# das48.net
KiCad netlist of a schematic drawn in EAGLE
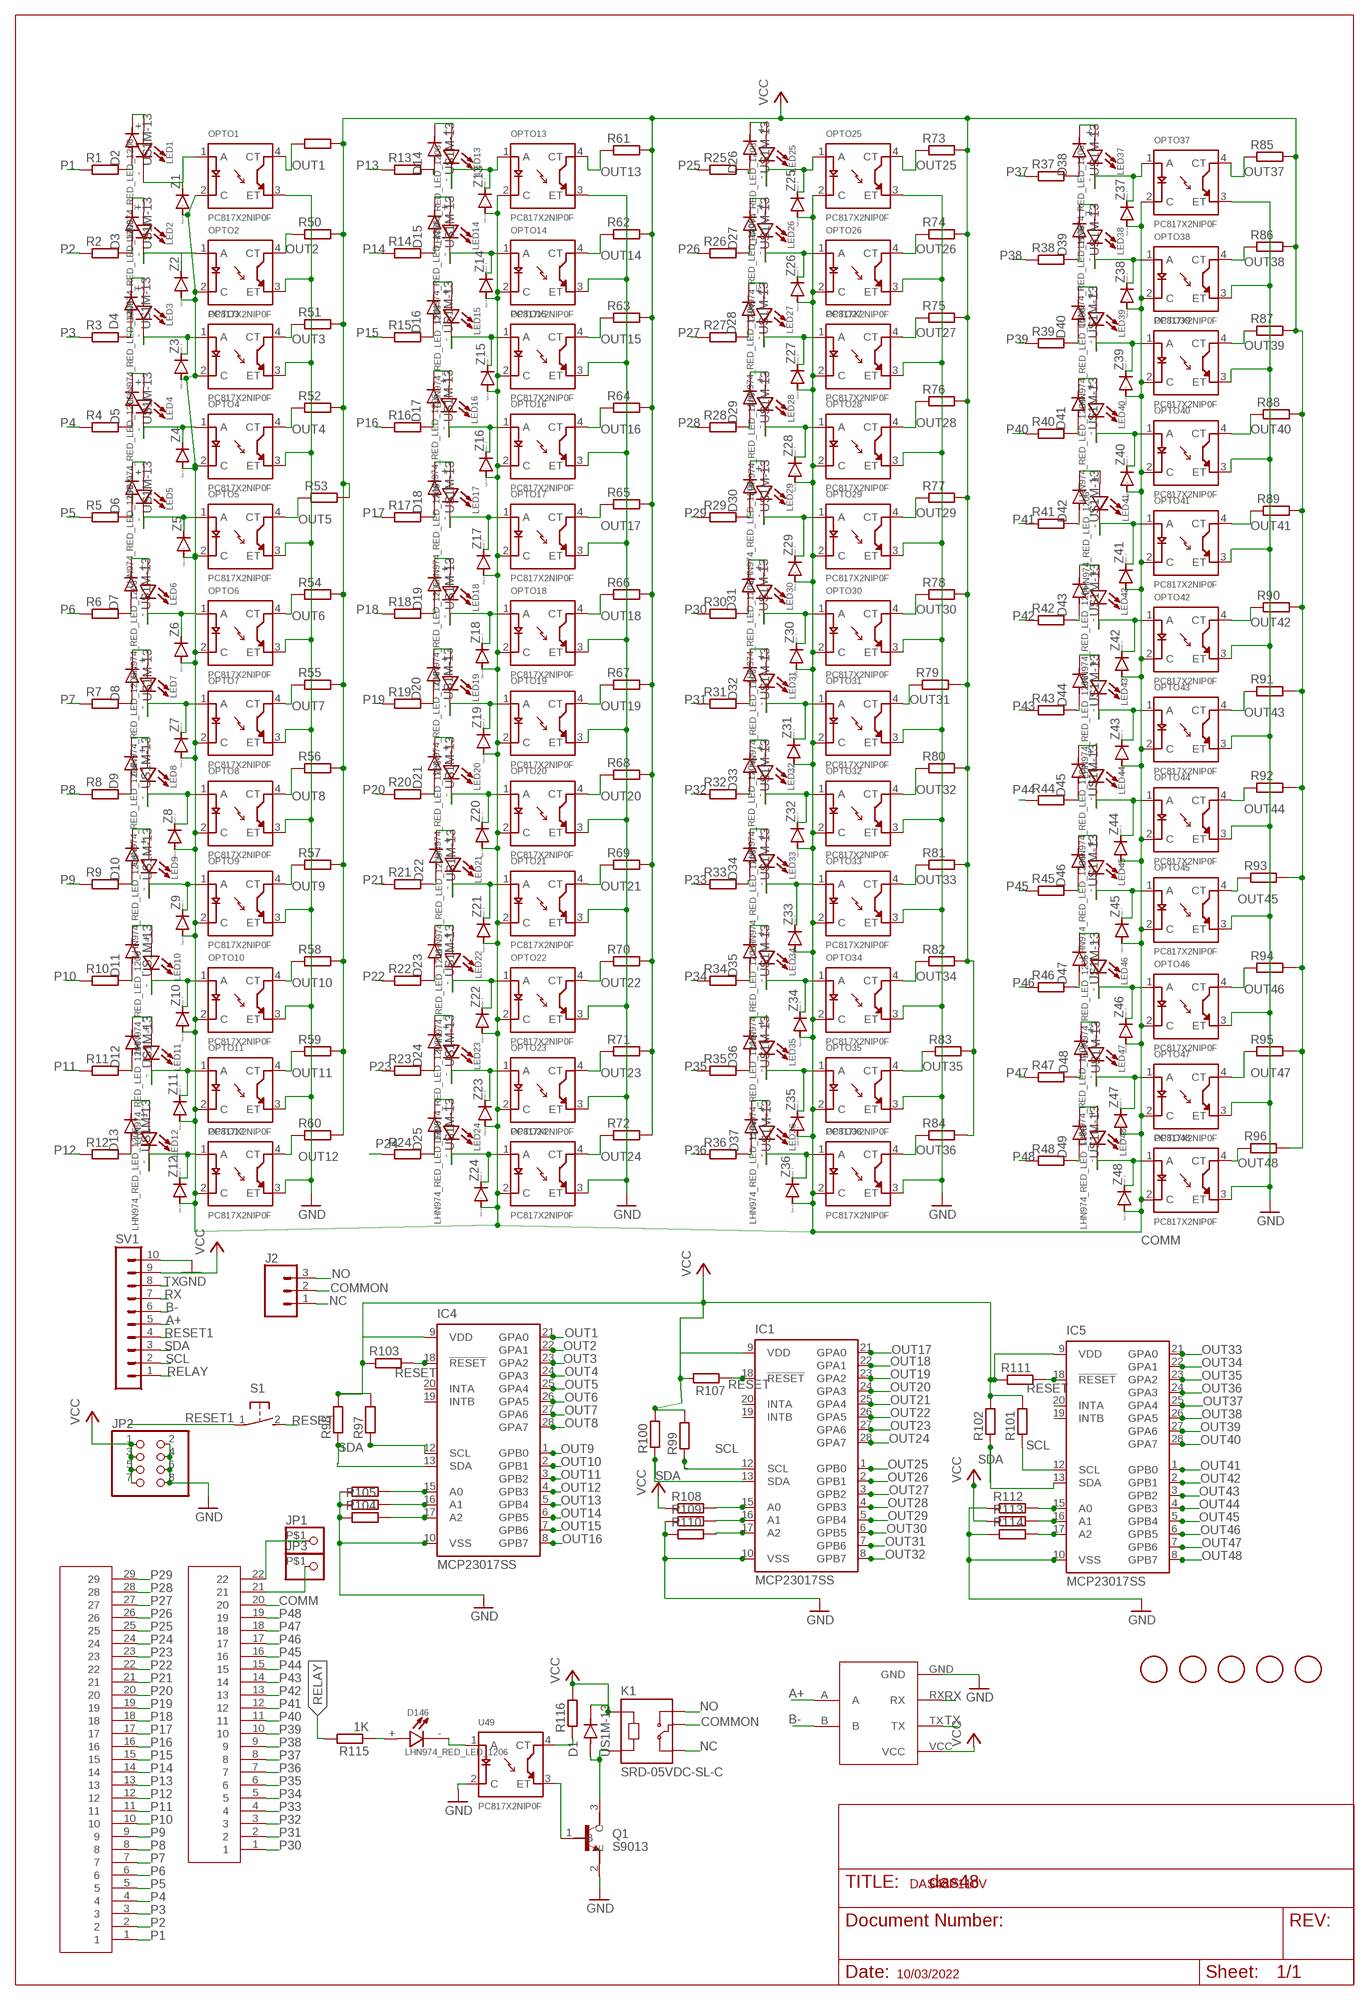
[diagram p0: schematic, sheet 1]

(export (version "E")
  (design (tool "Eeschema 10.0.6"))
  (components
    (comp (ref "D1")
      (value "US1M-13")
      (footprint "eagle-import:DIOM5226X240N")
      (fields (field (name "MF") "Diodes Incorporated"))
      (libsource (lib "eagle-import") (part "US1M-13"))
    )
    (comp (ref "D2")
      (value "US1M-13")
      (footprint "eagle-import:DIOM5226X240N")
      (fields (field (name "MF") "Diodes Incorporated"))
      (libsource (lib "eagle-import") (part "US1M-13"))
    )
    (comp (ref "D3")
      (value "US1M-13")
      (footprint "eagle-import:DIOM5226X240N")
      (fields (field (name "MF") "Diodes Incorporated"))
      (libsource (lib "eagle-import") (part "US1M-13"))
    )
    (comp (ref "D4")
      (value "US1M-13")
      (footprint "eagle-import:DIOM5226X240N")
      (fields (field (name "MF") "Diodes Incorporated"))
      (libsource (lib "eagle-import") (part "US1M-13"))
    )
    (comp (ref "D5")
      (value "US1M-13")
      (footprint "eagle-import:DIOM5226X240N")
      (fields (field (name "MF") "Diodes Incorporated"))
      (libsource (lib "eagle-import") (part "US1M-13"))
    )
    (comp (ref "D6")
      (value "US1M-13")
      (footprint "eagle-import:DIOM5226X240N")
      (fields (field (name "MF") "Diodes Incorporated"))
      (libsource (lib "eagle-import") (part "US1M-13"))
    )
    (comp (ref "D7")
      (value "US1M-13")
      (footprint "eagle-import:DIOM5226X240N")
      (fields (field (name "MF") "Diodes Incorporated"))
      (libsource (lib "eagle-import") (part "US1M-13"))
    )
    (comp (ref "D8")
      (value "US1M-13")
      (footprint "eagle-import:DIOM5226X240N")
      (fields (field (name "MF") "Diodes Incorporated"))
      (libsource (lib "eagle-import") (part "US1M-13"))
    )
    (comp (ref "D9")
      (value "US1M-13")
      (footprint "eagle-import:DIOM5226X240N")
      (fields (field (name "MF") "Diodes Incorporated"))
      (libsource (lib "eagle-import") (part "US1M-13"))
    )
    (comp (ref "D10")
      (value "US1M-13")
      (footprint "eagle-import:DIOM5226X240N")
      (fields (field (name "MF") "Diodes Incorporated"))
      (libsource (lib "eagle-import") (part "US1M-13"))
    )
    (comp (ref "D11")
      (value "US1M-13")
      (footprint "eagle-import:DIOM5226X240N")
      (fields (field (name "MF") "Diodes Incorporated"))
      (libsource (lib "eagle-import") (part "US1M-13"))
    )
    (comp (ref "D12")
      (value "US1M-13")
      (footprint "eagle-import:DIOM5226X240N")
      (fields (field (name "MF") "Diodes Incorporated"))
      (libsource (lib "eagle-import") (part "US1M-13"))
    )
    (comp (ref "D13")
      (value "US1M-13")
      (footprint "eagle-import:DIOM5226X240N")
      (fields (field (name "MF") "Diodes Incorporated"))
      (libsource (lib "eagle-import") (part "US1M-13"))
    )
    (comp (ref "D14")
      (value "US1M-13")
      (footprint "eagle-import:DIOM5226X240N")
      (fields (field (name "MF") "Diodes Incorporated"))
      (libsource (lib "eagle-import") (part "US1M-13"))
    )
    (comp (ref "D15")
      (value "US1M-13")
      (footprint "eagle-import:DIOM5226X240N")
      (fields (field (name "MF") "Diodes Incorporated"))
      (libsource (lib "eagle-import") (part "US1M-13"))
    )
    (comp (ref "D16")
      (value "US1M-13")
      (footprint "eagle-import:DIOM5226X240N")
      (fields (field (name "MF") "Diodes Incorporated"))
      (libsource (lib "eagle-import") (part "US1M-13"))
    )
    (comp (ref "D17")
      (value "US1M-13")
      (footprint "eagle-import:DIOM5226X240N")
      (fields (field (name "MF") "Diodes Incorporated"))
      (libsource (lib "eagle-import") (part "US1M-13"))
    )
    (comp (ref "D18")
      (value "US1M-13")
      (footprint "eagle-import:DIOM5226X240N")
      (fields (field (name "MF") "Diodes Incorporated"))
      (libsource (lib "eagle-import") (part "US1M-13"))
    )
    (comp (ref "D19")
      (value "US1M-13")
      (footprint "eagle-import:DIOM5226X240N")
      (fields (field (name "MF") "Diodes Incorporated"))
      (libsource (lib "eagle-import") (part "US1M-13"))
    )
    (comp (ref "D20")
      (value "US1M-13")
      (footprint "eagle-import:DIOM5226X240N")
      (fields (field (name "MF") "Diodes Incorporated"))
      (libsource (lib "eagle-import") (part "US1M-13"))
    )
    (comp (ref "D21")
      (value "US1M-13")
      (footprint "eagle-import:DIOM5226X240N")
      (fields (field (name "MF") "Diodes Incorporated"))
      (libsource (lib "eagle-import") (part "US1M-13"))
    )
    (comp (ref "D22")
      (value "US1M-13")
      (footprint "eagle-import:DIOM5226X240N")
      (fields (field (name "MF") "Diodes Incorporated"))
      (libsource (lib "eagle-import") (part "US1M-13"))
    )
    (comp (ref "D23")
      (value "US1M-13")
      (footprint "eagle-import:DIOM5226X240N")
      (fields (field (name "MF") "Diodes Incorporated"))
      (libsource (lib "eagle-import") (part "US1M-13"))
    )
    (comp (ref "D24")
      (value "US1M-13")
      (footprint "eagle-import:DIOM5226X240N")
      (fields (field (name "MF") "Diodes Incorporated"))
      (libsource (lib "eagle-import") (part "US1M-13"))
    )
    (comp (ref "D25")
      (value "US1M-13")
      (footprint "eagle-import:DIOM5226X240N")
      (fields (field (name "MF") "Diodes Incorporated"))
      (libsource (lib "eagle-import") (part "US1M-13"))
    )
    (comp (ref "D26")
      (value "US1M-13")
      (footprint "eagle-import:DIOM5226X240N")
      (fields (field (name "MF") "Diodes Incorporated"))
      (libsource (lib "eagle-import") (part "US1M-13"))
    )
    (comp (ref "D27")
      (value "US1M-13")
      (footprint "eagle-import:DIOM5226X240N")
      (fields (field (name "MF") "Diodes Incorporated"))
      (libsource (lib "eagle-import") (part "US1M-13"))
    )
    (comp (ref "D28")
      (value "US1M-13")
      (footprint "eagle-import:DIOM5226X240N")
      (fields (field (name "MF") "Diodes Incorporated"))
      (libsource (lib "eagle-import") (part "US1M-13"))
    )
    (comp (ref "D29")
      (value "US1M-13")
      (footprint "eagle-import:DIOM5226X240N")
      (fields (field (name "MF") "Diodes Incorporated"))
      (libsource (lib "eagle-import") (part "US1M-13"))
    )
    (comp (ref "D30")
      (value "US1M-13")
      (footprint "eagle-import:DIOM5226X240N")
      (fields (field (name "MF") "Diodes Incorporated"))
      (libsource (lib "eagle-import") (part "US1M-13"))
    )
    (comp (ref "D31")
      (value "US1M-13")
      (footprint "eagle-import:DIOM5226X240N")
      (fields (field (name "MF") "Diodes Incorporated"))
      (libsource (lib "eagle-import") (part "US1M-13"))
    )
    (comp (ref "D32")
      (value "US1M-13")
      (footprint "eagle-import:DIOM5226X240N")
      (fields (field (name "MF") "Diodes Incorporated"))
      (libsource (lib "eagle-import") (part "US1M-13"))
    )
    (comp (ref "D33")
      (value "US1M-13")
      (footprint "eagle-import:DIOM5226X240N")
      (fields (field (name "MF") "Diodes Incorporated"))
      (libsource (lib "eagle-import") (part "US1M-13"))
    )
    (comp (ref "D34")
      (value "US1M-13")
      (footprint "eagle-import:DIOM5226X240N")
      (fields (field (name "MF") "Diodes Incorporated"))
      (libsource (lib "eagle-import") (part "US1M-13"))
    )
    (comp (ref "D35")
      (value "US1M-13")
      (footprint "eagle-import:DIOM5226X240N")
      (fields (field (name "MF") "Diodes Incorporated"))
      (libsource (lib "eagle-import") (part "US1M-13"))
    )
    (comp (ref "D36")
      (value "US1M-13")
      (footprint "eagle-import:DIOM5226X240N")
      (fields (field (name "MF") "Diodes Incorporated"))
      (libsource (lib "eagle-import") (part "US1M-13"))
    )
    (comp (ref "D37")
      (value "US1M-13")
      (footprint "eagle-import:DIOM5226X240N")
      (fields (field (name "MF") "Diodes Incorporated"))
      (libsource (lib "eagle-import") (part "US1M-13"))
    )
    (comp (ref "D38")
      (value "US1M-13")
      (footprint "eagle-import:DIOM5226X240N")
      (fields (field (name "MF") "Diodes Incorporated"))
      (libsource (lib "eagle-import") (part "US1M-13"))
    )
    (comp (ref "D39")
      (value "US1M-13")
      (footprint "eagle-import:DIOM5226X240N")
      (fields (field (name "MF") "Diodes Incorporated"))
      (libsource (lib "eagle-import") (part "US1M-13"))
    )
    (comp (ref "D40")
      (value "US1M-13")
      (footprint "eagle-import:DIOM5226X240N")
      (fields (field (name "MF") "Diodes Incorporated"))
      (libsource (lib "eagle-import") (part "US1M-13"))
    )
    (comp (ref "D41")
      (value "US1M-13")
      (footprint "eagle-import:DIOM5226X240N")
      (fields (field (name "MF") "Diodes Incorporated"))
      (libsource (lib "eagle-import") (part "US1M-13"))
    )
    (comp (ref "D42")
      (value "US1M-13")
      (footprint "eagle-import:DIOM5226X240N")
      (fields (field (name "MF") "Diodes Incorporated"))
      (libsource (lib "eagle-import") (part "US1M-13"))
    )
    (comp (ref "D43")
      (value "US1M-13")
      (footprint "eagle-import:DIOM5226X240N")
      (fields (field (name "MF") "Diodes Incorporated"))
      (libsource (lib "eagle-import") (part "US1M-13"))
    )
    (comp (ref "D44")
      (value "US1M-13")
      (footprint "eagle-import:DIOM5226X240N")
      (fields (field (name "MF") "Diodes Incorporated"))
      (libsource (lib "eagle-import") (part "US1M-13"))
    )
    (comp (ref "D45")
      (value "US1M-13")
      (footprint "eagle-import:DIOM5226X240N")
      (fields (field (name "MF") "Diodes Incorporated"))
      (libsource (lib "eagle-import") (part "US1M-13"))
    )
    (comp (ref "D46")
      (value "US1M-13")
      (footprint "eagle-import:DIOM5226X240N")
      (fields (field (name "MF") "Diodes Incorporated"))
      (libsource (lib "eagle-import") (part "US1M-13"))
    )
    (comp (ref "D47")
      (value "US1M-13")
      (footprint "eagle-import:DIOM5226X240N")
      (fields (field (name "MF") "Diodes Incorporated"))
      (libsource (lib "eagle-import") (part "US1M-13"))
    )
    (comp (ref "D48")
      (value "US1M-13")
      (footprint "eagle-import:DIOM5226X240N")
      (fields (field (name "MF") "Diodes Incorporated"))
      (libsource (lib "eagle-import") (part "US1M-13"))
    )
    (comp (ref "D49")
      (value "US1M-13")
      (footprint "eagle-import:DIOM5226X240N")
      (fields (field (name "MF") "Diodes Incorporated"))
      (libsource (lib "eagle-import") (part "US1M-13"))
    )
    (comp (ref "D146")
      (value "LHN974_RED_LED_1206")
      (footprint "eagle-import:LEDC3216X120N")
      (fields (field (name "MF") "Osram") (field (name "MP") "LHN974 RED LED 1206"))
      (libsource (lib "eagle-import") (part "LHN974_RED_LED_1206"))
    )
    (comp (ref "HEADER-22P1")
      (value "HEADER-22P")
      (footprint "eagle-import:HEADER-29P")
      (libsource (lib "eagle-import") (part "HEADER-22P"))
    )
    (comp (ref "HEADER-29P1")
      (value "HEADER-29P")
      (footprint "eagle-import:HEADER-29P")
      (libsource (lib "eagle-import") (part "HEADER-29P"))
    )
    (comp (ref "IC1")
      (value "MCP23017SS")
      (footprint "eagle-import:SSOP28DB")
      (libsource (lib "eagle-import") (part "MCP23017SS"))
    )
    (comp (ref "IC4")
      (value "MCP23017SS")
      (footprint "eagle-import:SSOP28DB")
      (libsource (lib "eagle-import") (part "MCP23017SS"))
    )
    (comp (ref "IC5")
      (value "MCP23017SS")
      (footprint "eagle-import:SSOP28DB")
      (libsource (lib "eagle-import") (part "MCP23017SS"))
    )
    (comp (ref "J2")
      (value "CONN_03LONGPADS")
      (footprint "eagle-import:1X03_LONGPADS")
      (libsource (lib "eagle-import") (part "CONN_03LONGPADS"))
    )
    (comp (ref "JP1")
      (value "PINHD-1X1-BIGPOGO")
      (footprint "eagle-import:1X1-BIGPOGO")
      (libsource (lib "eagle-import") (part "PINHD-1X1-BIGPOGO"))
    )
    (comp (ref "JP2")
      (value "PINHD-2X4")
      (footprint "eagle-import:2X04")
      (libsource (lib "eagle-import") (part "PINHD-2X4"))
    )
    (comp (ref "JP3")
      (value "PINHD-1X1-BIGPOGO")
      (footprint "eagle-import:1X1-BIGPOGO")
      (libsource (lib "eagle-import") (part "PINHD-1X1-BIGPOGO"))
    )
    (comp (ref "K1")
      (value "SRD-05VDC-SL-C")
      (footprint "eagle-import:RELAY_SRD-05VDC-SL-C")
      (fields (field (name "MF") "Songle Relay"))
      (libsource (lib "eagle-import") (part "SRD-05VDC-SL-C"))
    )
    (comp (ref "LED1")
      (value "LHN974_RED_LED_1206")
      (footprint "eagle-import:LEDC3216X120N")
      (fields (field (name "MF") "Osram") (field (name "MP") "LHN974 RED LED 1206"))
      (libsource (lib "eagle-import") (part "LHN974_RED_LED_1206"))
    )
    (comp (ref "LED2")
      (value "LHN974_RED_LED_1206")
      (footprint "eagle-import:LEDC3216X120N")
      (fields (field (name "MF") "Osram") (field (name "MP") "LHN974 RED LED 1206"))
      (libsource (lib "eagle-import") (part "LHN974_RED_LED_1206"))
    )
    (comp (ref "LED3")
      (value "LHN974_RED_LED_1206")
      (footprint "eagle-import:LEDC3216X120N")
      (fields (field (name "MF") "Osram") (field (name "MP") "LHN974 RED LED 1206"))
      (libsource (lib "eagle-import") (part "LHN974_RED_LED_1206"))
    )
    (comp (ref "LED4")
      (value "LHN974_RED_LED_1206")
      (footprint "eagle-import:LEDC3216X120N")
      (fields (field (name "MF") "Osram") (field (name "MP") "LHN974 RED LED 1206"))
      (libsource (lib "eagle-import") (part "LHN974_RED_LED_1206"))
    )
    (comp (ref "LED5")
      (value "LHN974_RED_LED_1206")
      (footprint "eagle-import:LEDC3216X120N")
      (fields (field (name "MF") "Osram") (field (name "MP") "LHN974 RED LED 1206"))
      (libsource (lib "eagle-import") (part "LHN974_RED_LED_1206"))
    )
    (comp (ref "LED6")
      (value "LHN974_RED_LED_1206")
      (footprint "eagle-import:LEDC3216X120N")
      (fields (field (name "MF") "Osram") (field (name "MP") "LHN974 RED LED 1206"))
      (libsource (lib "eagle-import") (part "LHN974_RED_LED_1206"))
    )
    (comp (ref "LED7")
      (value "LHN974_RED_LED_1206")
      (footprint "eagle-import:LEDC3216X120N")
      (fields (field (name "MF") "Osram") (field (name "MP") "LHN974 RED LED 1206"))
      (libsource (lib "eagle-import") (part "LHN974_RED_LED_1206"))
    )
    (comp (ref "LED8")
      (value "LHN974_RED_LED_1206")
      (footprint "eagle-import:LEDC3216X120N")
      (fields (field (name "MF") "Osram") (field (name "MP") "LHN974 RED LED 1206"))
      (libsource (lib "eagle-import") (part "LHN974_RED_LED_1206"))
    )
    (comp (ref "LED9")
      (value "LHN974_RED_LED_1206")
      (footprint "eagle-import:LEDC3216X120N")
      (fields (field (name "MF") "Osram") (field (name "MP") "LHN974 RED LED 1206"))
      (libsource (lib "eagle-import") (part "LHN974_RED_LED_1206"))
    )
    (comp (ref "LED10")
      (value "LHN974_RED_LED_1206")
      (footprint "eagle-import:LEDC3216X120N")
      (fields (field (name "MF") "Osram") (field (name "MP") "LHN974 RED LED 1206"))
      (libsource (lib "eagle-import") (part "LHN974_RED_LED_1206"))
    )
    (comp (ref "LED11")
      (value "LHN974_RED_LED_1206")
      (footprint "eagle-import:LEDC3216X120N")
      (fields (field (name "MF") "Osram") (field (name "MP") "LHN974 RED LED 1206"))
      (libsource (lib "eagle-import") (part "LHN974_RED_LED_1206"))
    )
    (comp (ref "LED12")
      (value "LHN974_RED_LED_1206")
      (footprint "eagle-import:LEDC3216X120N")
      (fields (field (name "MF") "Osram") (field (name "MP") "LHN974 RED LED 1206"))
      (libsource (lib "eagle-import") (part "LHN974_RED_LED_1206"))
    )
    (comp (ref "LED13")
      (value "LHN974_RED_LED_1206")
      (footprint "eagle-import:LEDC3216X120N")
      (fields (field (name "MF") "Osram") (field (name "MP") "LHN974 RED LED 1206"))
      (libsource (lib "eagle-import") (part "LHN974_RED_LED_1206"))
    )
    (comp (ref "LED14")
      (value "LHN974_RED_LED_1206")
      (footprint "eagle-import:LEDC3216X120N")
      (fields (field (name "MF") "Osram") (field (name "MP") "LHN974 RED LED 1206"))
      (libsource (lib "eagle-import") (part "LHN974_RED_LED_1206"))
    )
    (comp (ref "LED15")
      (value "LHN974_RED_LED_1206")
      (footprint "eagle-import:LEDC3216X120N")
      (fields (field (name "MF") "Osram") (field (name "MP") "LHN974 RED LED 1206"))
      (libsource (lib "eagle-import") (part "LHN974_RED_LED_1206"))
    )
    (comp (ref "LED16")
      (value "LHN974_RED_LED_1206")
      (footprint "eagle-import:LEDC3216X120N")
      (fields (field (name "MF") "Osram") (field (name "MP") "LHN974 RED LED 1206"))
      (libsource (lib "eagle-import") (part "LHN974_RED_LED_1206"))
    )
    (comp (ref "LED17")
      (value "LHN974_RED_LED_1206")
      (footprint "eagle-import:LEDC3216X120N")
      (fields (field (name "MF") "Osram") (field (name "MP") "LHN974 RED LED 1206"))
      (libsource (lib "eagle-import") (part "LHN974_RED_LED_1206"))
    )
    (comp (ref "LED18")
      (value "LHN974_RED_LED_1206")
      (footprint "eagle-import:LEDC3216X120N")
      (fields (field (name "MF") "Osram") (field (name "MP") "LHN974 RED LED 1206"))
      (libsource (lib "eagle-import") (part "LHN974_RED_LED_1206"))
    )
    (comp (ref "LED19")
      (value "LHN974_RED_LED_1206")
      (footprint "eagle-import:LEDC3216X120N")
      (fields (field (name "MF") "Osram") (field (name "MP") "LHN974 RED LED 1206"))
      (libsource (lib "eagle-import") (part "LHN974_RED_LED_1206"))
    )
    (comp (ref "LED20")
      (value "LHN974_RED_LED_1206")
      (footprint "eagle-import:LEDC3216X120N")
      (fields (field (name "MF") "Osram") (field (name "MP") "LHN974 RED LED 1206"))
      (libsource (lib "eagle-import") (part "LHN974_RED_LED_1206"))
    )
    (comp (ref "LED21")
      (value "LHN974_RED_LED_1206")
      (footprint "eagle-import:LEDC3216X120N")
      (fields (field (name "MF") "Osram") (field (name "MP") "LHN974 RED LED 1206"))
      (libsource (lib "eagle-import") (part "LHN974_RED_LED_1206"))
    )
    (comp (ref "LED22")
      (value "LHN974_RED_LED_1206")
      (footprint "eagle-import:LEDC3216X120N")
      (fields (field (name "MF") "Osram") (field (name "MP") "LHN974 RED LED 1206"))
      (libsource (lib "eagle-import") (part "LHN974_RED_LED_1206"))
    )
    (comp (ref "LED23")
      (value "LHN974_RED_LED_1206")
      (footprint "eagle-import:LEDC3216X120N")
      (fields (field (name "MF") "Osram") (field (name "MP") "LHN974 RED LED 1206"))
      (libsource (lib "eagle-import") (part "LHN974_RED_LED_1206"))
    )
    (comp (ref "LED24")
      (value "LHN974_RED_LED_1206")
      (footprint "eagle-import:LEDC3216X120N")
      (fields (field (name "MF") "Osram") (field (name "MP") "LHN974 RED LED 1206"))
      (libsource (lib "eagle-import") (part "LHN974_RED_LED_1206"))
    )
    (comp (ref "LED25")
      (value "LHN974_RED_LED_1206")
      (footprint "eagle-import:LEDC3216X120N")
      (fields (field (name "MF") "Osram") (field (name "MP") "LHN974 RED LED 1206"))
      (libsource (lib "eagle-import") (part "LHN974_RED_LED_1206"))
    )
    (comp (ref "LED26")
      (value "LHN974_RED_LED_1206")
      (footprint "eagle-import:LEDC3216X120N")
      (fields (field (name "MF") "Osram") (field (name "MP") "LHN974 RED LED 1206"))
      (libsource (lib "eagle-import") (part "LHN974_RED_LED_1206"))
    )
    (comp (ref "LED27")
      (value "LHN974_RED_LED_1206")
      (footprint "eagle-import:LEDC3216X120N")
      (fields (field (name "MF") "Osram") (field (name "MP") "LHN974 RED LED 1206"))
      (libsource (lib "eagle-import") (part "LHN974_RED_LED_1206"))
    )
    (comp (ref "LED28")
      (value "LHN974_RED_LED_1206")
      (footprint "eagle-import:LEDC3216X120N")
      (fields (field (name "MF") "Osram") (field (name "MP") "LHN974 RED LED 1206"))
      (libsource (lib "eagle-import") (part "LHN974_RED_LED_1206"))
    )
    (comp (ref "LED29")
      (value "LHN974_RED_LED_1206")
      (footprint "eagle-import:LEDC3216X120N")
      (fields (field (name "MF") "Osram") (field (name "MP") "LHN974 RED LED 1206"))
      (libsource (lib "eagle-import") (part "LHN974_RED_LED_1206"))
    )
    (comp (ref "LED30")
      (value "LHN974_RED_LED_1206")
      (footprint "eagle-import:LEDC3216X120N")
      (fields (field (name "MF") "Osram") (field (name "MP") "LHN974 RED LED 1206"))
      (libsource (lib "eagle-import") (part "LHN974_RED_LED_1206"))
    )
    (comp (ref "LED31")
      (value "LHN974_RED_LED_1206")
      (footprint "eagle-import:LEDC3216X120N")
      (fields (field (name "MF") "Osram") (field (name "MP") "LHN974 RED LED 1206"))
      (libsource (lib "eagle-import") (part "LHN974_RED_LED_1206"))
    )
    (comp (ref "LED32")
      (value "LHN974_RED_LED_1206")
      (footprint "eagle-import:LEDC3216X120N")
      (fields (field (name "MF") "Osram") (field (name "MP") "LHN974 RED LED 1206"))
      (libsource (lib "eagle-import") (part "LHN974_RED_LED_1206"))
    )
    (comp (ref "LED33")
      (value "LHN974_RED_LED_1206")
      (footprint "eagle-import:LEDC3216X120N")
      (fields (field (name "MF") "Osram") (field (name "MP") "LHN974 RED LED 1206"))
      (libsource (lib "eagle-import") (part "LHN974_RED_LED_1206"))
    )
    (comp (ref "LED34")
      (value "LHN974_RED_LED_1206")
      (footprint "eagle-import:LEDC3216X120N")
      (fields (field (name "MF") "Osram") (field (name "MP") "LHN974 RED LED 1206"))
      (libsource (lib "eagle-import") (part "LHN974_RED_LED_1206"))
    )
    (comp (ref "LED35")
      (value "LHN974_RED_LED_1206")
      (footprint "eagle-import:LEDC3216X120N")
      (fields (field (name "MF") "Osram") (field (name "MP") "LHN974 RED LED 1206"))
      (libsource (lib "eagle-import") (part "LHN974_RED_LED_1206"))
    )
    (comp (ref "LED36")
      (value "LHN974_RED_LED_1206")
      (footprint "eagle-import:LEDC3216X120N")
      (fields (field (name "MF") "Osram") (field (name "MP") "LHN974 RED LED 1206"))
      (libsource (lib "eagle-import") (part "LHN974_RED_LED_1206"))
    )
    (comp (ref "LED37")
      (value "LHN974_RED_LED_1206")
      (footprint "eagle-import:LEDC3216X120N")
      (fields (field (name "MF") "Osram") (field (name "MP") "LHN974 RED LED 1206"))
      (libsource (lib "eagle-import") (part "LHN974_RED_LED_1206"))
    )
    (comp (ref "LED38")
      (value "LHN974_RED_LED_1206")
      (footprint "eagle-import:LEDC3216X120N")
      (fields (field (name "MF") "Osram") (field (name "MP") "LHN974 RED LED 1206"))
      (libsource (lib "eagle-import") (part "LHN974_RED_LED_1206"))
    )
    (comp (ref "LED39")
      (value "LHN974_RED_LED_1206")
      (footprint "eagle-import:LEDC3216X120N")
      (fields (field (name "MF") "Osram") (field (name "MP") "LHN974 RED LED 1206"))
      (libsource (lib "eagle-import") (part "LHN974_RED_LED_1206"))
    )
    (comp (ref "LED40")
      (value "LHN974_RED_LED_1206")
      (footprint "eagle-import:LEDC3216X120N")
      (fields (field (name "MF") "Osram") (field (name "MP") "LHN974 RED LED 1206"))
      (libsource (lib "eagle-import") (part "LHN974_RED_LED_1206"))
    )
    (comp (ref "LED41")
      (value "LHN974_RED_LED_1206")
      (footprint "eagle-import:LEDC3216X120N")
      (fields (field (name "MF") "Osram") (field (name "MP") "LHN974 RED LED 1206"))
      (libsource (lib "eagle-import") (part "LHN974_RED_LED_1206"))
    )
    (comp (ref "LED42")
      (value "LHN974_RED_LED_1206")
      (footprint "eagle-import:LEDC3216X120N")
      (fields (field (name "MF") "Osram") (field (name "MP") "LHN974 RED LED 1206"))
      (libsource (lib "eagle-import") (part "LHN974_RED_LED_1206"))
    )
    (comp (ref "LED43")
      (value "LHN974_RED_LED_1206")
      (footprint "eagle-import:LEDC3216X120N")
      (fields (field (name "MF") "Osram") (field (name "MP") "LHN974 RED LED 1206"))
      (libsource (lib "eagle-import") (part "LHN974_RED_LED_1206"))
    )
    (comp (ref "LED44")
      (value "LHN974_RED_LED_1206")
      (footprint "eagle-import:LEDC3216X120N")
      (fields (field (name "MF") "Osram") (field (name "MP") "LHN974 RED LED 1206"))
      (libsource (lib "eagle-import") (part "LHN974_RED_LED_1206"))
    )
    (comp (ref "LED45")
      (value "LHN974_RED_LED_1206")
      (footprint "eagle-import:LEDC3216X120N")
      (fields (field (name "MF") "Osram") (field (name "MP") "LHN974 RED LED 1206"))
      (libsource (lib "eagle-import") (part "LHN974_RED_LED_1206"))
    )
    (comp (ref "LED46")
      (value "LHN974_RED_LED_1206")
      (footprint "eagle-import:LEDC3216X120N")
      (fields (field (name "MF") "Osram") (field (name "MP") "LHN974 RED LED 1206"))
      (libsource (lib "eagle-import") (part "LHN974_RED_LED_1206"))
    )
    (comp (ref "LED47")
      (value "LHN974_RED_LED_1206")
      (footprint "eagle-import:LEDC3216X120N")
      (fields (field (name "MF") "Osram") (field (name "MP") "LHN974 RED LED 1206"))
      (libsource (lib "eagle-import") (part "LHN974_RED_LED_1206"))
    )
    (comp (ref "LED48")
      (value "LHN974_RED_LED_1206")
      (footprint "eagle-import:LEDC3216X120N")
      (fields (field (name "MF") "Osram") (field (name "MP") "LHN974 RED LED 1206"))
      (libsource (lib "eagle-import") (part "LHN974_RED_LED_1206"))
    )
    (comp (ref "OPTO1")
      (value "PC817X2NIP0F")
      (footprint "eagle-import:SOT254P975X400-4N")
      (fields (field (name "MF") "Sharp Microelectronics"))
      (libsource (lib "eagle-import") (part "PC817X2NIP0F"))
    )
    (comp (ref "OPTO2")
      (value "PC817X2NIP0F")
      (footprint "eagle-import:SOT254P975X400-4N")
      (fields (field (name "MF") "Sharp Microelectronics"))
      (libsource (lib "eagle-import") (part "PC817X2NIP0F"))
    )
    (comp (ref "OPTO3")
      (value "PC817X2NIP0F")
      (footprint "eagle-import:SOT254P975X400-4N")
      (fields (field (name "MF") "Sharp Microelectronics"))
      (libsource (lib "eagle-import") (part "PC817X2NIP0F"))
    )
    (comp (ref "OPTO4")
      (value "PC817X2NIP0F")
      (footprint "eagle-import:SOT254P975X400-4N")
      (fields (field (name "MF") "Sharp Microelectronics"))
      (libsource (lib "eagle-import") (part "PC817X2NIP0F"))
    )
    (comp (ref "OPTO5")
      (value "PC817X2NIP0F")
      (footprint "eagle-import:SOT254P975X400-4N")
      (fields (field (name "MF") "Sharp Microelectronics"))
      (libsource (lib "eagle-import") (part "PC817X2NIP0F"))
    )
    (comp (ref "OPTO6")
      (value "PC817X2NIP0F")
      (footprint "eagle-import:SOT254P975X400-4N")
      (fields (field (name "MF") "Sharp Microelectronics"))
      (libsource (lib "eagle-import") (part "PC817X2NIP0F"))
    )
    (comp (ref "OPTO7")
      (value "PC817X2NIP0F")
      (footprint "eagle-import:SOT254P975X400-4N")
      (fields (field (name "MF") "Sharp Microelectronics"))
      (libsource (lib "eagle-import") (part "PC817X2NIP0F"))
    )
    (comp (ref "OPTO8")
      (value "PC817X2NIP0F")
      (footprint "eagle-import:SOT254P975X400-4N")
      (fields (field (name "MF") "Sharp Microelectronics"))
      (libsource (lib "eagle-import") (part "PC817X2NIP0F"))
    )
    (comp (ref "OPTO9")
      (value "PC817X2NIP0F")
      (footprint "eagle-import:SOT254P975X400-4N")
      (fields (field (name "MF") "Sharp Microelectronics"))
      (libsource (lib "eagle-import") (part "PC817X2NIP0F"))
    )
    (comp (ref "OPTO10")
      (value "PC817X2NIP0F")
      (footprint "eagle-import:SOT254P975X400-4N")
      (fields (field (name "MF") "Sharp Microelectronics"))
      (libsource (lib "eagle-import") (part "PC817X2NIP0F"))
    )
    (comp (ref "OPTO11")
      (value "PC817X2NIP0F")
      (footprint "eagle-import:SOT254P975X400-4N")
      (fields (field (name "MF") "Sharp Microelectronics"))
      (libsource (lib "eagle-import") (part "PC817X2NIP0F"))
    )
    (comp (ref "OPTO12")
      (value "PC817X2NIP0F")
      (footprint "eagle-import:SOT254P975X400-4N")
      (fields (field (name "MF") "Sharp Microelectronics"))
      (libsource (lib "eagle-import") (part "PC817X2NIP0F"))
    )
    (comp (ref "OPTO13")
      (value "PC817X2NIP0F")
      (footprint "eagle-import:SOT254P975X400-4N")
      (fields (field (name "MF") "Sharp Microelectronics"))
      (libsource (lib "eagle-import") (part "PC817X2NIP0F"))
    )
    (comp (ref "OPTO14")
      (value "PC817X2NIP0F")
      (footprint "eagle-import:SOT254P975X400-4N")
      (fields (field (name "MF") "Sharp Microelectronics"))
      (libsource (lib "eagle-import") (part "PC817X2NIP0F"))
    )
    (comp (ref "OPTO15")
      (value "PC817X2NIP0F")
      (footprint "eagle-import:SOT254P975X400-4N")
      (fields (field (name "MF") "Sharp Microelectronics"))
      (libsource (lib "eagle-import") (part "PC817X2NIP0F"))
    )
    (comp (ref "OPTO16")
      (value "PC817X2NIP0F")
      (footprint "eagle-import:SOT254P975X400-4N")
      (fields (field (name "MF") "Sharp Microelectronics"))
      (libsource (lib "eagle-import") (part "PC817X2NIP0F"))
    )
    (comp (ref "OPTO17")
      (value "PC817X2NIP0F")
      (footprint "eagle-import:SOT254P975X400-4N")
      (fields (field (name "MF") "Sharp Microelectronics"))
      (libsource (lib "eagle-import") (part "PC817X2NIP0F"))
    )
    (comp (ref "OPTO18")
      (value "PC817X2NIP0F")
      (footprint "eagle-import:SOT254P975X400-4N")
      (fields (field (name "MF") "Sharp Microelectronics"))
      (libsource (lib "eagle-import") (part "PC817X2NIP0F"))
    )
    (comp (ref "OPTO19")
      (value "PC817X2NIP0F")
      (footprint "eagle-import:SOT254P975X400-4N")
      (fields (field (name "MF") "Sharp Microelectronics"))
      (libsource (lib "eagle-import") (part "PC817X2NIP0F"))
    )
    (comp (ref "OPTO20")
      (value "PC817X2NIP0F")
      (footprint "eagle-import:SOT254P975X400-4N")
      (fields (field (name "MF") "Sharp Microelectronics"))
      (libsource (lib "eagle-import") (part "PC817X2NIP0F"))
    )
    (comp (ref "OPTO21")
      (value "PC817X2NIP0F")
      (footprint "eagle-import:SOT254P975X400-4N")
      (fields (field (name "MF") "Sharp Microelectronics"))
      (libsource (lib "eagle-import") (part "PC817X2NIP0F"))
    )
    (comp (ref "OPTO22")
      (value "PC817X2NIP0F")
      (footprint "eagle-import:SOT254P975X400-4N")
      (fields (field (name "MF") "Sharp Microelectronics"))
      (libsource (lib "eagle-import") (part "PC817X2NIP0F"))
    )
    (comp (ref "OPTO23")
      (value "PC817X2NIP0F")
      (footprint "eagle-import:SOT254P975X400-4N")
      (fields (field (name "MF") "Sharp Microelectronics"))
      (libsource (lib "eagle-import") (part "PC817X2NIP0F"))
    )
    (comp (ref "OPTO24")
      (value "PC817X2NIP0F")
      (footprint "eagle-import:SOT254P975X400-4N")
      (fields (field (name "MF") "Sharp Microelectronics"))
      (libsource (lib "eagle-import") (part "PC817X2NIP0F"))
    )
    (comp (ref "OPTO25")
      (value "PC817X2NIP0F")
      (footprint "eagle-import:SOT254P975X400-4N")
      (fields (field (name "MF") "Sharp Microelectronics"))
      (libsource (lib "eagle-import") (part "PC817X2NIP0F"))
    )
    (comp (ref "OPTO26")
      (value "PC817X2NIP0F")
      (footprint "eagle-import:SOT254P975X400-4N")
      (fields (field (name "MF") "Sharp Microelectronics"))
      (libsource (lib "eagle-import") (part "PC817X2NIP0F"))
    )
    (comp (ref "OPTO27")
      (value "PC817X2NIP0F")
      (footprint "eagle-import:SOT254P975X400-4N")
      (fields (field (name "MF") "Sharp Microelectronics"))
      (libsource (lib "eagle-import") (part "PC817X2NIP0F"))
    )
    (comp (ref "OPTO28")
      (value "PC817X2NIP0F")
      (footprint "eagle-import:SOT254P975X400-4N")
      (fields (field (name "MF") "Sharp Microelectronics"))
      (libsource (lib "eagle-import") (part "PC817X2NIP0F"))
    )
    (comp (ref "OPTO29")
      (value "PC817X2NIP0F")
      (footprint "eagle-import:SOT254P975X400-4N")
      (fields (field (name "MF") "Sharp Microelectronics"))
      (libsource (lib "eagle-import") (part "PC817X2NIP0F"))
    )
    (comp (ref "OPTO30")
      (value "PC817X2NIP0F")
      (footprint "eagle-import:SOT254P975X400-4N")
      (fields (field (name "MF") "Sharp Microelectronics"))
      (libsource (lib "eagle-import") (part "PC817X2NIP0F"))
    )
    (comp (ref "OPTO31")
      (value "PC817X2NIP0F")
      (footprint "eagle-import:SOT254P975X400-4N")
      (fields (field (name "MF") "Sharp Microelectronics"))
      (libsource (lib "eagle-import") (part "PC817X2NIP0F"))
    )
    (comp (ref "OPTO32")
      (value "PC817X2NIP0F")
      (footprint "eagle-import:SOT254P975X400-4N")
      (fields (field (name "MF") "Sharp Microelectronics"))
      (libsource (lib "eagle-import") (part "PC817X2NIP0F"))
    )
    (comp (ref "OPTO33")
      (value "PC817X2NIP0F")
      (footprint "eagle-import:SOT254P975X400-4N")
      (fields (field (name "MF") "Sharp Microelectronics"))
      (libsource (lib "eagle-import") (part "PC817X2NIP0F"))
    )
    (comp (ref "OPTO34")
      (value "PC817X2NIP0F")
      (footprint "eagle-import:SOT254P975X400-4N")
      (fields (field (name "MF") "Sharp Microelectronics"))
      (libsource (lib "eagle-import") (part "PC817X2NIP0F"))
    )
    (comp (ref "OPTO35")
      (value "PC817X2NIP0F")
      (footprint "eagle-import:SOT254P975X400-4N")
      (fields (field (name "MF") "Sharp Microelectronics"))
      (libsource (lib "eagle-import") (part "PC817X2NIP0F"))
    )
    (comp (ref "OPTO36")
      (value "PC817X2NIP0F")
      (footprint "eagle-import:SOT254P975X400-4N")
      (fields (field (name "MF") "Sharp Microelectronics"))
      (libsource (lib "eagle-import") (part "PC817X2NIP0F"))
    )
    (comp (ref "OPTO37")
      (value "PC817X2NIP0F")
      (footprint "eagle-import:SOT254P975X400-4N")
      (fields (field (name "MF") "Sharp Microelectronics"))
      (libsource (lib "eagle-import") (part "PC817X2NIP0F"))
    )
    (comp (ref "OPTO38")
      (value "PC817X2NIP0F")
      (footprint "eagle-import:SOT254P975X400-4N")
      (fields (field (name "MF") "Sharp Microelectronics"))
      (libsource (lib "eagle-import") (part "PC817X2NIP0F"))
    )
    (comp (ref "OPTO39")
      (value "PC817X2NIP0F")
      (footprint "eagle-import:SOT254P975X400-4N")
      (fields (field (name "MF") "Sharp Microelectronics"))
      (libsource (lib "eagle-import") (part "PC817X2NIP0F"))
    )
    (comp (ref "OPTO40")
      (value "PC817X2NIP0F")
      (footprint "eagle-import:SOT254P975X400-4N")
      (fields (field (name "MF") "Sharp Microelectronics"))
      (libsource (lib "eagle-import") (part "PC817X2NIP0F"))
    )
    (comp (ref "OPTO41")
      (value "PC817X2NIP0F")
      (footprint "eagle-import:SOT254P975X400-4N")
      (fields (field (name "MF") "Sharp Microelectronics"))
      (libsource (lib "eagle-import") (part "PC817X2NIP0F"))
    )
    (comp (ref "OPTO42")
      (value "PC817X2NIP0F")
      (footprint "eagle-import:SOT254P975X400-4N")
      (fields (field (name "MF") "Sharp Microelectronics"))
      (libsource (lib "eagle-import") (part "PC817X2NIP0F"))
    )
    (comp (ref "OPTO43")
      (value "PC817X2NIP0F")
      (footprint "eagle-import:SOT254P975X400-4N")
      (fields (field (name "MF") "Sharp Microelectronics"))
      (libsource (lib "eagle-import") (part "PC817X2NIP0F"))
    )
    (comp (ref "OPTO44")
      (value "PC817X2NIP0F")
      (footprint "eagle-import:SOT254P975X400-4N")
      (fields (field (name "MF") "Sharp Microelectronics"))
      (libsource (lib "eagle-import") (part "PC817X2NIP0F"))
    )
    (comp (ref "OPTO45")
      (value "PC817X2NIP0F")
      (footprint "eagle-import:SOT254P975X400-4N")
      (fields (field (name "MF") "Sharp Microelectronics"))
      (libsource (lib "eagle-import") (part "PC817X2NIP0F"))
    )
    (comp (ref "OPTO46")
      (value "PC817X2NIP0F")
      (footprint "eagle-import:SOT254P975X400-4N")
      (fields (field (name "MF") "Sharp Microelectronics"))
      (libsource (lib "eagle-import") (part "PC817X2NIP0F"))
    )
    (comp (ref "OPTO47")
      (value "PC817X2NIP0F")
      (footprint "eagle-import:SOT254P975X400-4N")
      (fields (field (name "MF") "Sharp Microelectronics"))
      (libsource (lib "eagle-import") (part "PC817X2NIP0F"))
    )
    (comp (ref "OPTO48")
      (value "PC817X2NIP0F")
      (footprint "eagle-import:SOT254P975X400-4N")
      (fields (field (name "MF") "Sharp Microelectronics"))
      (libsource (lib "eagle-import") (part "PC817X2NIP0F"))
    )
    (comp (ref "Q1")
      (value "S9013")
      (footprint "eagle-import:SOT95P240X120-3N")
      (fields (field (name "MF") "JCET"))
      (libsource (lib "eagle-import") (part "S9013"))
    )
    (comp (ref "R1")
      (value "R-EU_0617/17")
      (footprint "eagle-import:0617_17")
      (libsource (lib "eagle-import") (part "R-EU_0617/17"))
    )
    (comp (ref "R2")
      (value "R-EU_0617/17")
      (footprint "eagle-import:0617_17")
      (libsource (lib "eagle-import") (part "R-EU_0617/17"))
    )
    (comp (ref "R3")
      (value "R-EU_0617/17")
      (footprint "eagle-import:0617_17")
      (libsource (lib "eagle-import") (part "R-EU_0617/17"))
    )
    (comp (ref "R4")
      (value "R-EU_0617/17")
      (footprint "eagle-import:0617_17")
      (libsource (lib "eagle-import") (part "R-EU_0617/17"))
    )
    (comp (ref "R5")
      (value "R-EU_0617/17")
      (footprint "eagle-import:0617_17")
      (libsource (lib "eagle-import") (part "R-EU_0617/17"))
    )
    (comp (ref "R6")
      (value "R-EU_0617/17")
      (footprint "eagle-import:0617_17")
      (libsource (lib "eagle-import") (part "R-EU_0617/17"))
    )
    (comp (ref "R7")
      (value "R-EU_0617/17")
      (footprint "eagle-import:0617_17")
      (libsource (lib "eagle-import") (part "R-EU_0617/17"))
    )
    (comp (ref "R8")
      (value "R-EU_0617/17")
      (footprint "eagle-import:0617_17")
      (libsource (lib "eagle-import") (part "R-EU_0617/17"))
    )
    (comp (ref "R9")
      (value "R-EU_0617/17")
      (footprint "eagle-import:0617_17")
      (libsource (lib "eagle-import") (part "R-EU_0617/17"))
    )
    (comp (ref "R10")
      (value "R-EU_0617/17")
      (footprint "eagle-import:0617_17")
      (libsource (lib "eagle-import") (part "R-EU_0617/17"))
    )
    (comp (ref "R11")
      (value "R-EU_0617/17")
      (footprint "eagle-import:0617_17")
      (libsource (lib "eagle-import") (part "R-EU_0617/17"))
    )
    (comp (ref "R12")
      (value "R-EU_0617/17")
      (footprint "eagle-import:0617_17")
      (libsource (lib "eagle-import") (part "R-EU_0617/17"))
    )
    (comp (ref "R13")
      (value "R-EU_0617/17")
      (footprint "eagle-import:0617_17")
      (libsource (lib "eagle-import") (part "R-EU_0617/17"))
    )
    (comp (ref "R14")
      (value "R-EU_0617/17")
      (footprint "eagle-import:0617_17")
      (libsource (lib "eagle-import") (part "R-EU_0617/17"))
    )
    (comp (ref "R15")
      (value "R-EU_0617/17")
      (footprint "eagle-import:0617_17")
      (libsource (lib "eagle-import") (part "R-EU_0617/17"))
    )
    (comp (ref "R16")
      (value "R-EU_0617/17")
      (footprint "eagle-import:0617_17")
      (libsource (lib "eagle-import") (part "R-EU_0617/17"))
    )
    (comp (ref "R17")
      (value "R-EU_0617/17")
      (footprint "eagle-import:0617_17")
      (libsource (lib "eagle-import") (part "R-EU_0617/17"))
    )
    (comp (ref "R18")
      (value "R-EU_0617/17")
      (footprint "eagle-import:0617_17")
      (libsource (lib "eagle-import") (part "R-EU_0617/17"))
    )
    (comp (ref "R19")
      (value "R-EU_0617/17")
      (footprint "eagle-import:0617_17")
      (libsource (lib "eagle-import") (part "R-EU_0617/17"))
    )
    (comp (ref "R20")
      (value "R-EU_0617/17")
      (footprint "eagle-import:0617_17")
      (libsource (lib "eagle-import") (part "R-EU_0617/17"))
    )
    (comp (ref "R21")
      (value "R-EU_0617/17")
      (footprint "eagle-import:0617_17")
      (libsource (lib "eagle-import") (part "R-EU_0617/17"))
    )
    (comp (ref "R22")
      (value "R-EU_0617/17")
      (footprint "eagle-import:0617_17")
      (libsource (lib "eagle-import") (part "R-EU_0617/17"))
    )
    (comp (ref "R23")
      (value "R-EU_0617/17")
      (footprint "eagle-import:0617_17")
      (libsource (lib "eagle-import") (part "R-EU_0617/17"))
    )
    (comp (ref "R24")
      (value "R-EU_0617/17")
      (footprint "eagle-import:0617_17")
      (libsource (lib "eagle-import") (part "R-EU_0617/17"))
    )
    (comp (ref "R25")
      (value "R-EU_0617/17")
      (footprint "eagle-import:0617_17")
      (libsource (lib "eagle-import") (part "R-EU_0617/17"))
    )
    (comp (ref "R26")
      (value "R-EU_0617/17")
      (footprint "eagle-import:0617_17")
      (libsource (lib "eagle-import") (part "R-EU_0617/17"))
    )
    (comp (ref "R27")
      (value "R-EU_0617/17")
      (footprint "eagle-import:0617_17")
      (libsource (lib "eagle-import") (part "R-EU_0617/17"))
    )
    (comp (ref "R28")
      (value "R-EU_0617/17")
      (footprint "eagle-import:0617_17")
      (libsource (lib "eagle-import") (part "R-EU_0617/17"))
    )
    (comp (ref "R29")
      (value "R-EU_0617/17")
      (footprint "eagle-import:0617_17")
      (libsource (lib "eagle-import") (part "R-EU_0617/17"))
    )
    (comp (ref "R30")
      (value "R-EU_0617/17")
      (footprint "eagle-import:0617_17")
      (libsource (lib "eagle-import") (part "R-EU_0617/17"))
    )
    (comp (ref "R31")
      (value "R-EU_0617/17")
      (footprint "eagle-import:0617_17")
      (libsource (lib "eagle-import") (part "R-EU_0617/17"))
    )
    (comp (ref "R32")
      (value "R-EU_0617/17")
      (footprint "eagle-import:0617_17")
      (libsource (lib "eagle-import") (part "R-EU_0617/17"))
    )
    (comp (ref "R33")
      (value "R-EU_0617/17")
      (footprint "eagle-import:0617_17")
      (libsource (lib "eagle-import") (part "R-EU_0617/17"))
    )
    (comp (ref "R34")
      (value "R-EU_0617/17")
      (footprint "eagle-import:0617_17")
      (libsource (lib "eagle-import") (part "R-EU_0617/17"))
    )
    (comp (ref "R35")
      (value "R-EU_0617/17")
      (footprint "eagle-import:0617_17")
      (libsource (lib "eagle-import") (part "R-EU_0617/17"))
    )
    (comp (ref "R36")
      (value "R-EU_0617/17")
      (footprint "eagle-import:0617_17")
      (libsource (lib "eagle-import") (part "R-EU_0617/17"))
    )
    (comp (ref "R37")
      (value "R-EU_0617/17")
      (footprint "eagle-import:0617_17")
      (libsource (lib "eagle-import") (part "R-EU_0617/17"))
    )
    (comp (ref "R38")
      (value "R-EU_0617/17")
      (footprint "eagle-import:0617_17")
      (libsource (lib "eagle-import") (part "R-EU_0617/17"))
    )
    (comp (ref "R39")
      (value "R-EU_0617/17")
      (footprint "eagle-import:0617_17")
      (libsource (lib "eagle-import") (part "R-EU_0617/17"))
    )
    (comp (ref "R40")
      (value "R-EU_0617/17")
      (footprint "eagle-import:0617_17")
      (libsource (lib "eagle-import") (part "R-EU_0617/17"))
    )
    (comp (ref "R41")
      (value "R-EU_0617/17")
      (footprint "eagle-import:0617_17")
      (libsource (lib "eagle-import") (part "R-EU_0617/17"))
    )
    (comp (ref "R42")
      (value "R-EU_0617/17")
      (footprint "eagle-import:0617_17")
      (libsource (lib "eagle-import") (part "R-EU_0617/17"))
    )
    (comp (ref "R43")
      (value "R-EU_0617/17")
      (footprint "eagle-import:0617_17")
      (libsource (lib "eagle-import") (part "R-EU_0617/17"))
    )
    (comp (ref "R44")
      (value "R-EU_0617/17")
      (footprint "eagle-import:0617_17")
      (libsource (lib "eagle-import") (part "R-EU_0617/17"))
    )
    (comp (ref "R45")
      (value "R-EU_0617/17")
      (footprint "eagle-import:0617_17")
      (libsource (lib "eagle-import") (part "R-EU_0617/17"))
    )
    (comp (ref "R46")
      (value "R-EU_0617/17")
      (footprint "eagle-import:0617_17")
      (libsource (lib "eagle-import") (part "R-EU_0617/17"))
    )
    (comp (ref "R47")
      (value "R-EU_0617/17")
      (footprint "eagle-import:0617_17")
      (libsource (lib "eagle-import") (part "R-EU_0617/17"))
    )
    (comp (ref "R48")
      (value "R-EU_0617/17")
      (footprint "eagle-import:0617_17")
      (libsource (lib "eagle-import") (part "R-EU_0617/17"))
    )
    (comp (ref "R49")
      (value "R-EU_R0805")
      (footprint "eagle-import:R0805")
      (libsource (lib "eagle-import") (part "R-EU_R0805"))
    )
    (comp (ref "R50")
      (value "R-EU_R0805")
      (footprint "eagle-import:R0805")
      (libsource (lib "eagle-import") (part "R-EU_R0805"))
    )
    (comp (ref "R51")
      (value "R-EU_R0805")
      (footprint "eagle-import:R0805")
      (libsource (lib "eagle-import") (part "R-EU_R0805"))
    )
    (comp (ref "R52")
      (value "R-EU_R0805")
      (footprint "eagle-import:R0805")
      (libsource (lib "eagle-import") (part "R-EU_R0805"))
    )
    (comp (ref "R53")
      (value "R-EU_R0805")
      (footprint "eagle-import:R0805")
      (libsource (lib "eagle-import") (part "R-EU_R0805"))
    )
    (comp (ref "R54")
      (value "R-EU_R0805")
      (footprint "eagle-import:R0805")
      (libsource (lib "eagle-import") (part "R-EU_R0805"))
    )
    (comp (ref "R55")
      (value "R-EU_R0805")
      (footprint "eagle-import:R0805")
      (libsource (lib "eagle-import") (part "R-EU_R0805"))
    )
    (comp (ref "R56")
      (value "R-EU_R0805")
      (footprint "eagle-import:R0805")
      (libsource (lib "eagle-import") (part "R-EU_R0805"))
    )
    (comp (ref "R57")
      (value "R-EU_R0805")
      (footprint "eagle-import:R0805")
      (libsource (lib "eagle-import") (part "R-EU_R0805"))
    )
    (comp (ref "R58")
      (value "R-EU_R0805")
      (footprint "eagle-import:R0805")
      (libsource (lib "eagle-import") (part "R-EU_R0805"))
    )
    (comp (ref "R59")
      (value "R-EU_R0805")
      (footprint "eagle-import:R0805")
      (libsource (lib "eagle-import") (part "R-EU_R0805"))
    )
    (comp (ref "R60")
      (value "R-EU_R0805")
      (footprint "eagle-import:R0805")
      (libsource (lib "eagle-import") (part "R-EU_R0805"))
    )
    (comp (ref "R61")
      (value "R-EU_R0805")
      (footprint "eagle-import:R0805")
      (libsource (lib "eagle-import") (part "R-EU_R0805"))
    )
    (comp (ref "R62")
      (value "R-EU_R0805")
      (footprint "eagle-import:R0805")
      (libsource (lib "eagle-import") (part "R-EU_R0805"))
    )
    (comp (ref "R63")
      (value "R-EU_R0805")
      (footprint "eagle-import:R0805")
      (libsource (lib "eagle-import") (part "R-EU_R0805"))
    )
    (comp (ref "R64")
      (value "R-EU_R0805")
      (footprint "eagle-import:R0805")
      (libsource (lib "eagle-import") (part "R-EU_R0805"))
    )
    (comp (ref "R65")
      (value "R-EU_R0805")
      (footprint "eagle-import:R0805")
      (libsource (lib "eagle-import") (part "R-EU_R0805"))
    )
    (comp (ref "R66")
      (value "R-EU_R0805")
      (footprint "eagle-import:R0805")
      (libsource (lib "eagle-import") (part "R-EU_R0805"))
    )
    (comp (ref "R67")
      (value "R-EU_R0805")
      (footprint "eagle-import:R0805")
      (libsource (lib "eagle-import") (part "R-EU_R0805"))
    )
    (comp (ref "R68")
      (value "R-EU_R0805")
      (footprint "eagle-import:R0805")
      (libsource (lib "eagle-import") (part "R-EU_R0805"))
    )
    (comp (ref "R69")
      (value "R-EU_R0805")
      (footprint "eagle-import:R0805")
      (libsource (lib "eagle-import") (part "R-EU_R0805"))
    )
    (comp (ref "R70")
      (value "R-EU_R0805")
      (footprint "eagle-import:R0805")
      (libsource (lib "eagle-import") (part "R-EU_R0805"))
    )
    (comp (ref "R71")
      (value "R-EU_R0805")
      (footprint "eagle-import:R0805")
      (libsource (lib "eagle-import") (part "R-EU_R0805"))
    )
    (comp (ref "R72")
      (value "R-EU_R0805")
      (footprint "eagle-import:R0805")
      (libsource (lib "eagle-import") (part "R-EU_R0805"))
    )
    (comp (ref "R73")
      (value "R-EU_R0805")
      (footprint "eagle-import:R0805")
      (libsource (lib "eagle-import") (part "R-EU_R0805"))
    )
    (comp (ref "R74")
      (value "R-EU_R0805")
      (footprint "eagle-import:R0805")
      (libsource (lib "eagle-import") (part "R-EU_R0805"))
    )
    (comp (ref "R75")
      (value "R-EU_R0805")
      (footprint "eagle-import:R0805")
      (libsource (lib "eagle-import") (part "R-EU_R0805"))
    )
    (comp (ref "R76")
      (value "R-EU_R0805")
      (footprint "eagle-import:R0805")
      (libsource (lib "eagle-import") (part "R-EU_R0805"))
    )
    (comp (ref "R77")
      (value "R-EU_R0805")
      (footprint "eagle-import:R0805")
      (libsource (lib "eagle-import") (part "R-EU_R0805"))
    )
    (comp (ref "R78")
      (value "R-EU_R0805")
      (footprint "eagle-import:R0805")
      (libsource (lib "eagle-import") (part "R-EU_R0805"))
    )
    (comp (ref "R79")
      (value "R-EU_R0805")
      (footprint "eagle-import:R0805")
      (libsource (lib "eagle-import") (part "R-EU_R0805"))
    )
    (comp (ref "R80")
      (value "R-EU_R0805")
      (footprint "eagle-import:R0805")
      (libsource (lib "eagle-import") (part "R-EU_R0805"))
    )
    (comp (ref "R81")
      (value "R-EU_R0805")
      (footprint "eagle-import:R0805")
      (libsource (lib "eagle-import") (part "R-EU_R0805"))
    )
    (comp (ref "R82")
      (value "R-EU_R0805")
      (footprint "eagle-import:R0805")
      (libsource (lib "eagle-import") (part "R-EU_R0805"))
    )
    (comp (ref "R83")
      (value "R-EU_R0805")
      (footprint "eagle-import:R0805")
      (libsource (lib "eagle-import") (part "R-EU_R0805"))
    )
    (comp (ref "R84")
      (value "R-EU_R0805")
      (footprint "eagle-import:R0805")
      (libsource (lib "eagle-import") (part "R-EU_R0805"))
    )
    (comp (ref "R85")
      (value "R-EU_R0805")
      (footprint "eagle-import:R0805")
      (libsource (lib "eagle-import") (part "R-EU_R0805"))
    )
    (comp (ref "R86")
      (value "R-EU_R0805")
      (footprint "eagle-import:R0805")
      (libsource (lib "eagle-import") (part "R-EU_R0805"))
    )
    (comp (ref "R87")
      (value "R-EU_R0805")
      (footprint "eagle-import:R0805")
      (libsource (lib "eagle-import") (part "R-EU_R0805"))
    )
    (comp (ref "R88")
      (value "R-EU_R0805")
      (footprint "eagle-import:R0805")
      (libsource (lib "eagle-import") (part "R-EU_R0805"))
    )
    (comp (ref "R89")
      (value "R-EU_R0805")
      (footprint "eagle-import:R0805")
      (libsource (lib "eagle-import") (part "R-EU_R0805"))
    )
    (comp (ref "R90")
      (value "R-EU_R0805")
      (footprint "eagle-import:R0805")
      (libsource (lib "eagle-import") (part "R-EU_R0805"))
    )
    (comp (ref "R91")
      (value "R-EU_R0805")
      (footprint "eagle-import:R0805")
      (libsource (lib "eagle-import") (part "R-EU_R0805"))
    )
    (comp (ref "R92")
      (value "R-EU_R0805")
      (footprint "eagle-import:R0805")
      (libsource (lib "eagle-import") (part "R-EU_R0805"))
    )
    (comp (ref "R93")
      (value "R-EU_R0805")
      (footprint "eagle-import:R0805")
      (libsource (lib "eagle-import") (part "R-EU_R0805"))
    )
    (comp (ref "R94")
      (value "R-EU_R0805")
      (footprint "eagle-import:R0805")
      (libsource (lib "eagle-import") (part "R-EU_R0805"))
    )
    (comp (ref "R95")
      (value "R-EU_R0805")
      (footprint "eagle-import:R0805")
      (libsource (lib "eagle-import") (part "R-EU_R0805"))
    )
    (comp (ref "R96")
      (value "R-EU_R0805")
      (footprint "eagle-import:R0805")
      (libsource (lib "eagle-import") (part "R-EU_R0805"))
    )
    (comp (ref "R97")
      (value "R-EU_R0805")
      (footprint "eagle-import:R0805")
      (libsource (lib "eagle-import") (part "R-EU_R0805"))
    )
    (comp (ref "R98")
      (value "R-EU_R0805")
      (footprint "eagle-import:R0805")
      (libsource (lib "eagle-import") (part "R-EU_R0805"))
    )
    (comp (ref "R99")
      (value "R-EU_R0805")
      (footprint "eagle-import:R0805")
      (libsource (lib "eagle-import") (part "R-EU_R0805"))
    )
    (comp (ref "R100")
      (value "R-EU_R0805")
      (footprint "eagle-import:R0805")
      (libsource (lib "eagle-import") (part "R-EU_R0805"))
    )
    (comp (ref "R101")
      (value "R-EU_R0805")
      (footprint "eagle-import:R0805")
      (libsource (lib "eagle-import") (part "R-EU_R0805"))
    )
    (comp (ref "R102")
      (value "R-EU_R0805")
      (footprint "eagle-import:R0805")
      (libsource (lib "eagle-import") (part "R-EU_R0805"))
    )
    (comp (ref "R103")
      (value "R-EU_R0805")
      (footprint "eagle-import:R0805")
      (libsource (lib "eagle-import") (part "R-EU_R0805"))
    )
    (comp (ref "R104")
      (value "R-EU_R0805")
      (footprint "eagle-import:R0805")
      (libsource (lib "eagle-import") (part "R-EU_R0805"))
    )
    (comp (ref "R105")
      (value "R-EU_R0805")
      (footprint "eagle-import:R0805")
      (libsource (lib "eagle-import") (part "R-EU_R0805"))
    )
    (comp (ref "R106")
      (value "R-EU_R0805")
      (footprint "eagle-import:R0805")
      (libsource (lib "eagle-import") (part "R-EU_R0805"))
    )
    (comp (ref "R107")
      (value "R-EU_R0805")
      (footprint "eagle-import:R0805")
      (libsource (lib "eagle-import") (part "R-EU_R0805"))
    )
    (comp (ref "R108")
      (value "R-EU_R0805")
      (footprint "eagle-import:R0805")
      (libsource (lib "eagle-import") (part "R-EU_R0805"))
    )
    (comp (ref "R109")
      (value "R-EU_R0805")
      (footprint "eagle-import:R0805")
      (libsource (lib "eagle-import") (part "R-EU_R0805"))
    )
    (comp (ref "R110")
      (value "R-EU_R0805")
      (footprint "eagle-import:R0805")
      (libsource (lib "eagle-import") (part "R-EU_R0805"))
    )
    (comp (ref "R111")
      (value "R-EU_R0805")
      (footprint "eagle-import:R0805")
      (libsource (lib "eagle-import") (part "R-EU_R0805"))
    )
    (comp (ref "R112")
      (value "R-EU_R0805")
      (footprint "eagle-import:R0805")
      (libsource (lib "eagle-import") (part "R-EU_R0805"))
    )
    (comp (ref "R113")
      (value "R-EU_R0805")
      (footprint "eagle-import:R0805")
      (libsource (lib "eagle-import") (part "R-EU_R0805"))
    )
    (comp (ref "R114")
      (value "R-EU_R0805")
      (footprint "eagle-import:R0805")
      (libsource (lib "eagle-import") (part "R-EU_R0805"))
    )
    (comp (ref "R115")
      (value "1K")
      (footprint "eagle-import:R0805")
      (libsource (lib "eagle-import") (part "R-EU_R0805"))
    )
    (comp (ref "R116")
      (value "R-EU_R0805")
      (footprint "eagle-import:R0805")
      (libsource (lib "eagle-import") (part "R-EU_R0805"))
    )
    (comp (ref "S1")
      (value "31-XX")
      (footprint "eagle-import:B3F-31XX")
      (fields (field (name "MPN") "B3F-3100"))
      (libsource (lib "eagle-import") (part "31-XX"))
    )
    (comp (ref "SV1")
      (value "MA10-1")
      (footprint "eagle-import:MA10-1")
      (libsource (lib "eagle-import") (part "MA10-1"))
    )
    (comp (ref "TTL-RS1")
      (value "TTL-RS485")
      (footprint "eagle-import:TTL-RS485")
      (libsource (lib "eagle-import") (part "TTL-RS485"))
    )
    (comp (ref "U$1")
      (value "FIDUCIAL")
      (footprint "eagle-import:FIDUCIAL_1MM")
      (libsource (lib "eagle-import") (part "FIDUCIAL"))
    )
    (comp (ref "U$2")
      (value "FIDUCIAL")
      (footprint "eagle-import:FIDUCIAL_1MM")
      (libsource (lib "eagle-import") (part "FIDUCIAL"))
    )
    (comp (ref "U$3")
      (value "FIDUCIAL")
      (footprint "eagle-import:FIDUCIAL_1MM")
      (libsource (lib "eagle-import") (part "FIDUCIAL"))
    )
    (comp (ref "U$4")
      (value "FIDUCIAL")
      (footprint "eagle-import:FIDUCIAL_1MM")
      (libsource (lib "eagle-import") (part "FIDUCIAL"))
    )
    (comp (ref "U$5")
      (value "FIDUCIAL")
      (footprint "eagle-import:FIDUCIAL_1MM")
      (libsource (lib "eagle-import") (part "FIDUCIAL"))
    )
    (comp (ref "U49")
      (value "PC817X2NIP0F")
      (footprint "eagle-import:SOT254P975X400-4N")
      (fields (field (name "MF") "Sharp Microelectronics"))
      (libsource (lib "eagle-import") (part "PC817X2NIP0F"))
    )
    (comp (ref "Z1")
      (value "DIODE-SOD123")
      (footprint "eagle-import:SOD123")
      (libsource (lib "eagle-import") (part "DIODE-SOD123"))
    )
    (comp (ref "Z2")
      (value "DIODE-SOD123")
      (footprint "eagle-import:SOD123")
      (libsource (lib "eagle-import") (part "DIODE-SOD123"))
    )
    (comp (ref "Z3")
      (value "DIODE-SOD123")
      (footprint "eagle-import:SOD123")
      (libsource (lib "eagle-import") (part "DIODE-SOD123"))
    )
    (comp (ref "Z4")
      (value "DIODE-SOD123")
      (footprint "eagle-import:SOD123")
      (libsource (lib "eagle-import") (part "DIODE-SOD123"))
    )
    (comp (ref "Z5")
      (value "DIODE-SOD123")
      (footprint "eagle-import:SOD123")
      (libsource (lib "eagle-import") (part "DIODE-SOD123"))
    )
    (comp (ref "Z6")
      (value "DIODE-SOD123")
      (footprint "eagle-import:SOD123")
      (libsource (lib "eagle-import") (part "DIODE-SOD123"))
    )
    (comp (ref "Z7")
      (value "DIODE-SOD123")
      (footprint "eagle-import:SOD123")
      (libsource (lib "eagle-import") (part "DIODE-SOD123"))
    )
    (comp (ref "Z8")
      (value "DIODE-SOD123")
      (footprint "eagle-import:SOD123")
      (libsource (lib "eagle-import") (part "DIODE-SOD123"))
    )
    (comp (ref "Z9")
      (value "DIODE-SOD123")
      (footprint "eagle-import:SOD123")
      (libsource (lib "eagle-import") (part "DIODE-SOD123"))
    )
    (comp (ref "Z10")
      (value "DIODE-SOD123")
      (footprint "eagle-import:SOD123")
      (libsource (lib "eagle-import") (part "DIODE-SOD123"))
    )
    (comp (ref "Z11")
      (value "DIODE-SOD123")
      (footprint "eagle-import:SOD123")
      (libsource (lib "eagle-import") (part "DIODE-SOD123"))
    )
    (comp (ref "Z12")
      (value "DIODE-SOD123")
      (footprint "eagle-import:SOD123")
      (libsource (lib "eagle-import") (part "DIODE-SOD123"))
    )
    (comp (ref "Z13")
      (value "DIODE-SOD123")
      (footprint "eagle-import:SOD123")
      (libsource (lib "eagle-import") (part "DIODE-SOD123"))
    )
    (comp (ref "Z14")
      (value "DIODE-SOD123")
      (footprint "eagle-import:SOD123")
      (libsource (lib "eagle-import") (part "DIODE-SOD123"))
    )
    (comp (ref "Z15")
      (value "DIODE-SOD123")
      (footprint "eagle-import:SOD123")
      (libsource (lib "eagle-import") (part "DIODE-SOD123"))
    )
    (comp (ref "Z16")
      (value "DIODE-SOD123")
      (footprint "eagle-import:SOD123")
      (libsource (lib "eagle-import") (part "DIODE-SOD123"))
    )
    (comp (ref "Z17")
      (value "DIODE-SOD123")
      (footprint "eagle-import:SOD123")
      (libsource (lib "eagle-import") (part "DIODE-SOD123"))
    )
    (comp (ref "Z18")
      (value "DIODE-SOD123")
      (footprint "eagle-import:SOD123")
      (libsource (lib "eagle-import") (part "DIODE-SOD123"))
    )
    (comp (ref "Z19")
      (value "DIODE-SOD123")
      (footprint "eagle-import:SOD123")
      (libsource (lib "eagle-import") (part "DIODE-SOD123"))
    )
    (comp (ref "Z20")
      (value "DIODE-SOD123")
      (footprint "eagle-import:SOD123")
      (libsource (lib "eagle-import") (part "DIODE-SOD123"))
    )
    (comp (ref "Z21")
      (value "DIODE-SOD123")
      (footprint "eagle-import:SOD123")
      (libsource (lib "eagle-import") (part "DIODE-SOD123"))
    )
    (comp (ref "Z22")
      (value "DIODE-SOD123")
      (footprint "eagle-import:SOD123")
      (libsource (lib "eagle-import") (part "DIODE-SOD123"))
    )
    (comp (ref "Z23")
      (value "DIODE-SOD123")
      (footprint "eagle-import:SOD123")
      (libsource (lib "eagle-import") (part "DIODE-SOD123"))
    )
    (comp (ref "Z24")
      (value "DIODE-SOD123")
      (footprint "eagle-import:SOD123")
      (libsource (lib "eagle-import") (part "DIODE-SOD123"))
    )
    (comp (ref "Z25")
      (value "DIODE-SOD123")
      (footprint "eagle-import:SOD123")
      (libsource (lib "eagle-import") (part "DIODE-SOD123"))
    )
    (comp (ref "Z26")
      (value "DIODE-SOD123")
      (footprint "eagle-import:SOD123")
      (libsource (lib "eagle-import") (part "DIODE-SOD123"))
    )
    (comp (ref "Z27")
      (value "DIODE-SOD123")
      (footprint "eagle-import:SOD123")
      (libsource (lib "eagle-import") (part "DIODE-SOD123"))
    )
    (comp (ref "Z28")
      (value "DIODE-SOD123")
      (footprint "eagle-import:SOD123")
      (libsource (lib "eagle-import") (part "DIODE-SOD123"))
    )
    (comp (ref "Z29")
      (value "DIODE-SOD123")
      (footprint "eagle-import:SOD123")
      (libsource (lib "eagle-import") (part "DIODE-SOD123"))
    )
    (comp (ref "Z30")
      (value "DIODE-SOD123")
      (footprint "eagle-import:SOD123")
      (libsource (lib "eagle-import") (part "DIODE-SOD123"))
    )
    (comp (ref "Z31")
      (value "DIODE-SOD123")
      (footprint "eagle-import:SOD123")
      (libsource (lib "eagle-import") (part "DIODE-SOD123"))
    )
    (comp (ref "Z32")
      (value "DIODE-SOD123")
      (footprint "eagle-import:SOD123")
      (libsource (lib "eagle-import") (part "DIODE-SOD123"))
    )
    (comp (ref "Z33")
      (value "DIODE-SOD123")
      (footprint "eagle-import:SOD123")
      (libsource (lib "eagle-import") (part "DIODE-SOD123"))
    )
    (comp (ref "Z34")
      (value "DIODE-SOD123")
      (footprint "eagle-import:SOD123")
      (libsource (lib "eagle-import") (part "DIODE-SOD123"))
    )
    (comp (ref "Z35")
      (value "DIODE-SOD123")
      (footprint "eagle-import:SOD123")
      (libsource (lib "eagle-import") (part "DIODE-SOD123"))
    )
    (comp (ref "Z36")
      (value "DIODE-SOD123")
      (footprint "eagle-import:SOD123")
      (libsource (lib "eagle-import") (part "DIODE-SOD123"))
    )
    (comp (ref "Z37")
      (value "DIODE-SOD123")
      (footprint "eagle-import:SOD123")
      (libsource (lib "eagle-import") (part "DIODE-SOD123"))
    )
    (comp (ref "Z38")
      (value "DIODE-SOD123")
      (footprint "eagle-import:SOD123")
      (libsource (lib "eagle-import") (part "DIODE-SOD123"))
    )
    (comp (ref "Z39")
      (value "DIODE-SOD123")
      (footprint "eagle-import:SOD123")
      (libsource (lib "eagle-import") (part "DIODE-SOD123"))
    )
    (comp (ref "Z40")
      (value "DIODE-SOD123")
      (footprint "eagle-import:SOD123")
      (libsource (lib "eagle-import") (part "DIODE-SOD123"))
    )
    (comp (ref "Z41")
      (value "DIODE-SOD123")
      (footprint "eagle-import:SOD123")
      (libsource (lib "eagle-import") (part "DIODE-SOD123"))
    )
    (comp (ref "Z42")
      (value "DIODE-SOD123")
      (footprint "eagle-import:SOD123")
      (libsource (lib "eagle-import") (part "DIODE-SOD123"))
    )
    (comp (ref "Z43")
      (value "DIODE-SOD123")
      (footprint "eagle-import:SOD123")
      (libsource (lib "eagle-import") (part "DIODE-SOD123"))
    )
    (comp (ref "Z44")
      (value "DIODE-SOD123")
      (footprint "eagle-import:SOD123")
      (libsource (lib "eagle-import") (part "DIODE-SOD123"))
    )
    (comp (ref "Z45")
      (value "DIODE-SOD123")
      (footprint "eagle-import:SOD123")
      (libsource (lib "eagle-import") (part "DIODE-SOD123"))
    )
    (comp (ref "Z46")
      (value "DIODE-SOD123")
      (footprint "eagle-import:SOD123")
      (libsource (lib "eagle-import") (part "DIODE-SOD123"))
    )
    (comp (ref "Z47")
      (value "DIODE-SOD123")
      (footprint "eagle-import:SOD123")
      (libsource (lib "eagle-import") (part "DIODE-SOD123"))
    )
    (comp (ref "Z48")
      (value "DIODE-SOD123")
      (footprint "eagle-import:SOD123")
      (libsource (lib "eagle-import") (part "DIODE-SOD123"))
    )
  )
  (nets
    (net (code "1") (name "/A+") (class "Default")
      (node (ref "SV1") (pin "5") (pinfunction "5_5") (pintype "passive"))
      (node (ref "TTL-RS1") (pin "A") (pinfunction "A_A") (pintype "bidirectional"))
    )
    (net (code "2") (name "/B-") (class "Default")
      (node (ref "SV1") (pin "6") (pinfunction "6_6") (pintype "passive"))
      (node (ref "TTL-RS1") (pin "B") (pinfunction "B_B") (pintype "bidirectional"))
    )
    (net (code "3") (name "/COMM") (class "Default")
      (node (ref "HEADER-22P1") (pin "20") (pinfunction "20_20") (pintype "bidirectional"))
      (node (ref "OPTO1") (pin "2") (pinfunction "C_2") (pintype "passive"))
      (node (ref "OPTO10") (pin "2") (pinfunction "C_2") (pintype "passive"))
      (node (ref "OPTO11") (pin "2") (pinfunction "C_2") (pintype "passive"))
      (node (ref "OPTO12") (pin "2") (pinfunction "C_2") (pintype "passive"))
      (node (ref "OPTO13") (pin "2") (pinfunction "C_2") (pintype "passive"))
      (node (ref "OPTO14") (pin "2") (pinfunction "C_2") (pintype "passive"))
      (node (ref "OPTO15") (pin "2") (pinfunction "C_2") (pintype "passive"))
      (node (ref "OPTO16") (pin "2") (pinfunction "C_2") (pintype "passive"))
      (node (ref "OPTO17") (pin "2") (pinfunction "C_2") (pintype "passive"))
      (node (ref "OPTO18") (pin "2") (pinfunction "C_2") (pintype "passive"))
      (node (ref "OPTO19") (pin "2") (pinfunction "C_2") (pintype "passive"))
      (node (ref "OPTO2") (pin "2") (pinfunction "C_2") (pintype "passive"))
      (node (ref "OPTO20") (pin "2") (pinfunction "C_2") (pintype "passive"))
      (node (ref "OPTO21") (pin "2") (pinfunction "C_2") (pintype "passive"))
      (node (ref "OPTO22") (pin "2") (pinfunction "C_2") (pintype "passive"))
      (node (ref "OPTO23") (pin "2") (pinfunction "C_2") (pintype "passive"))
      (node (ref "OPTO24") (pin "2") (pinfunction "C_2") (pintype "passive"))
      (node (ref "OPTO25") (pin "2") (pinfunction "C_2") (pintype "passive"))
      (node (ref "OPTO26") (pin "2") (pinfunction "C_2") (pintype "passive"))
      (node (ref "OPTO27") (pin "2") (pinfunction "C_2") (pintype "passive"))
      (node (ref "OPTO28") (pin "2") (pinfunction "C_2") (pintype "passive"))
      (node (ref "OPTO29") (pin "2") (pinfunction "C_2") (pintype "passive"))
      (node (ref "OPTO3") (pin "2") (pinfunction "C_2") (pintype "passive"))
      (node (ref "OPTO30") (pin "2") (pinfunction "C_2") (pintype "passive"))
      (node (ref "OPTO31") (pin "2") (pinfunction "C_2") (pintype "passive"))
      (node (ref "OPTO32") (pin "2") (pinfunction "C_2") (pintype "passive"))
      (node (ref "OPTO33") (pin "2") (pinfunction "C_2") (pintype "passive"))
      (node (ref "OPTO34") (pin "2") (pinfunction "C_2") (pintype "passive"))
      (node (ref "OPTO35") (pin "2") (pinfunction "C_2") (pintype "passive"))
      (node (ref "OPTO36") (pin "2") (pinfunction "C_2") (pintype "passive"))
      (node (ref "OPTO37") (pin "2") (pinfunction "C_2") (pintype "passive"))
      (node (ref "OPTO38") (pin "2") (pinfunction "C_2") (pintype "passive"))
      (node (ref "OPTO39") (pin "2") (pinfunction "C_2") (pintype "passive"))
      (node (ref "OPTO4") (pin "2") (pinfunction "C_2") (pintype "passive"))
      (node (ref "OPTO40") (pin "2") (pinfunction "C_2") (pintype "passive"))
      (node (ref "OPTO41") (pin "2") (pinfunction "C_2") (pintype "passive"))
      (node (ref "OPTO42") (pin "2") (pinfunction "C_2") (pintype "passive"))
      (node (ref "OPTO43") (pin "2") (pinfunction "C_2") (pintype "passive"))
      (node (ref "OPTO44") (pin "2") (pinfunction "C_2") (pintype "passive"))
      (node (ref "OPTO45") (pin "2") (pinfunction "C_2") (pintype "passive"))
      (node (ref "OPTO46") (pin "2") (pinfunction "C_2") (pintype "passive"))
      (node (ref "OPTO47") (pin "2") (pinfunction "C_2") (pintype "passive"))
      (node (ref "OPTO48") (pin "2") (pinfunction "C_2") (pintype "passive"))
      (node (ref "OPTO5") (pin "2") (pinfunction "C_2") (pintype "passive"))
      (node (ref "OPTO6") (pin "2") (pinfunction "C_2") (pintype "passive"))
      (node (ref "OPTO7") (pin "2") (pinfunction "C_2") (pintype "passive"))
      (node (ref "OPTO8") (pin "2") (pinfunction "C_2") (pintype "passive"))
      (node (ref "OPTO9") (pin "2") (pinfunction "C_2") (pintype "passive"))
      (node (ref "Z1") (pin "A") (pinfunction "A_A") (pintype "passive"))
      (node (ref "Z10") (pin "A") (pinfunction "A_A") (pintype "passive"))
      (node (ref "Z11") (pin "A") (pinfunction "A_A") (pintype "passive"))
      (node (ref "Z12") (pin "A") (pinfunction "A_A") (pintype "passive"))
      (node (ref "Z13") (pin "A") (pinfunction "A_A") (pintype "passive"))
      (node (ref "Z14") (pin "A") (pinfunction "A_A") (pintype "passive"))
      (node (ref "Z15") (pin "A") (pinfunction "A_A") (pintype "passive"))
      (node (ref "Z16") (pin "A") (pinfunction "A_A") (pintype "passive"))
      (node (ref "Z17") (pin "A") (pinfunction "A_A") (pintype "passive"))
      (node (ref "Z18") (pin "A") (pinfunction "A_A") (pintype "passive"))
      (node (ref "Z19") (pin "A") (pinfunction "A_A") (pintype "passive"))
      (node (ref "Z2") (pin "A") (pinfunction "A_A") (pintype "passive"))
      (node (ref "Z20") (pin "A") (pinfunction "A_A") (pintype "passive"))
      (node (ref "Z21") (pin "A") (pinfunction "A_A") (pintype "passive"))
      (node (ref "Z22") (pin "A") (pinfunction "A_A") (pintype "passive"))
      (node (ref "Z23") (pin "A") (pinfunction "A_A") (pintype "passive"))
      (node (ref "Z24") (pin "A") (pinfunction "A_A") (pintype "passive"))
      (node (ref "Z25") (pin "A") (pinfunction "A_A") (pintype "passive"))
      (node (ref "Z26") (pin "A") (pinfunction "A_A") (pintype "passive"))
      (node (ref "Z27") (pin "A") (pinfunction "A_A") (pintype "passive"))
      (node (ref "Z28") (pin "A") (pinfunction "A_A") (pintype "passive"))
      (node (ref "Z29") (pin "A") (pinfunction "A_A") (pintype "passive"))
      (node (ref "Z3") (pin "A") (pinfunction "A_A") (pintype "passive"))
      (node (ref "Z30") (pin "A") (pinfunction "A_A") (pintype "passive"))
      (node (ref "Z31") (pin "A") (pinfunction "A_A") (pintype "passive"))
      (node (ref "Z32") (pin "A") (pinfunction "A_A") (pintype "passive"))
      (node (ref "Z33") (pin "A") (pinfunction "A_A") (pintype "passive"))
      (node (ref "Z34") (pin "A") (pinfunction "A_A") (pintype "passive"))
      (node (ref "Z35") (pin "A") (pinfunction "A_A") (pintype "passive"))
      (node (ref "Z36") (pin "A") (pinfunction "A_A") (pintype "passive"))
      (node (ref "Z37") (pin "A") (pinfunction "A_A") (pintype "passive"))
      (node (ref "Z38") (pin "A") (pinfunction "A_A") (pintype "passive"))
      (node (ref "Z39") (pin "A") (pinfunction "A_A") (pintype "passive"))
      (node (ref "Z4") (pin "A") (pinfunction "A_A") (pintype "passive"))
      (node (ref "Z40") (pin "A") (pinfunction "A_A") (pintype "passive"))
      (node (ref "Z41") (pin "A") (pinfunction "A_A") (pintype "passive"))
      (node (ref "Z42") (pin "A") (pinfunction "A_A") (pintype "passive"))
      (node (ref "Z43") (pin "A") (pinfunction "A_A") (pintype "passive"))
      (node (ref "Z44") (pin "A") (pinfunction "A_A") (pintype "passive"))
      (node (ref "Z45") (pin "A") (pinfunction "A_A") (pintype "passive"))
      (node (ref "Z46") (pin "A") (pinfunction "A_A") (pintype "passive"))
      (node (ref "Z47") (pin "A") (pinfunction "A_A") (pintype "passive"))
      (node (ref "Z48") (pin "A") (pinfunction "A_A") (pintype "passive"))
      (node (ref "Z5") (pin "A") (pinfunction "A_A") (pintype "passive"))
      (node (ref "Z6") (pin "A") (pinfunction "A_A") (pintype "passive"))
      (node (ref "Z7") (pin "A") (pinfunction "A_A") (pintype "passive"))
      (node (ref "Z8") (pin "A") (pinfunction "A_A") (pintype "passive"))
      (node (ref "Z9") (pin "A") (pinfunction "A_A") (pintype "passive"))
    )
    (net (code "4") (name "/COMMON") (class "Default")
      (node (ref "J2") (pin "2") (pinfunction "2_2") (pintype "passive"))
      (node (ref "K1") (pin "COM") (pinfunction "COM_COM") (pintype "passive"))
    )
    (net (code "5") (name "/NC") (class "Default")
      (node (ref "J2") (pin "1") (pinfunction "1_1") (pintype "passive"))
      (node (ref "K1") (pin "NC") (pinfunction "NC_NC") (pintype "passive"))
    )
    (net (code "6") (name "/NO") (class "Default")
      (node (ref "J2") (pin "3") (pinfunction "3_3") (pintype "passive"))
      (node (ref "K1") (pin "NO") (pinfunction "NO_NO") (pintype "passive"))
    )
    (net (code "7") (name "/OUT1") (class "Default")
      (node (ref "IC4") (pin "21") (pinfunction "GPA0_21") (pintype "bidirectional"))
      (node (ref "OPTO1") (pin "4") (pinfunction "CT_4") (pintype "passive"))
      (node (ref "R49") (pin "1") (pinfunction "1_1") (pintype "passive"))
    )
    (net (code "8") (name "/OUT2") (class "Default")
      (node (ref "IC4") (pin "22") (pinfunction "GPA1_22") (pintype "bidirectional"))
      (node (ref "OPTO2") (pin "4") (pinfunction "CT_4") (pintype "passive"))
      (node (ref "R50") (pin "1") (pinfunction "1_1") (pintype "passive"))
    )
    (net (code "9") (name "/OUT3") (class "Default")
      (node (ref "IC4") (pin "23") (pinfunction "GPA2_23") (pintype "bidirectional"))
      (node (ref "OPTO3") (pin "4") (pinfunction "CT_4") (pintype "passive"))
      (node (ref "R51") (pin "1") (pinfunction "1_1") (pintype "passive"))
    )
    (net (code "10") (name "/OUT4") (class "Default")
      (node (ref "IC4") (pin "24") (pinfunction "GPA3_24") (pintype "bidirectional"))
      (node (ref "OPTO4") (pin "4") (pinfunction "CT_4") (pintype "passive"))
      (node (ref "R52") (pin "1") (pinfunction "1_1") (pintype "passive"))
    )
    (net (code "11") (name "/OUT5") (class "Default")
      (node (ref "IC4") (pin "25") (pinfunction "GPA4_25") (pintype "bidirectional"))
      (node (ref "OPTO5") (pin "4") (pinfunction "CT_4") (pintype "passive"))
      (node (ref "R53") (pin "1") (pinfunction "1_1") (pintype "passive"))
    )
    (net (code "12") (name "/OUT6") (class "Default")
      (node (ref "IC4") (pin "26") (pinfunction "GPA5_26") (pintype "bidirectional"))
      (node (ref "OPTO6") (pin "4") (pinfunction "CT_4") (pintype "passive"))
      (node (ref "R54") (pin "1") (pinfunction "1_1") (pintype "passive"))
    )
    (net (code "13") (name "/OUT7") (class "Default")
      (node (ref "IC4") (pin "27") (pinfunction "GPA6_27") (pintype "bidirectional"))
      (node (ref "OPTO7") (pin "4") (pinfunction "CT_4") (pintype "passive"))
      (node (ref "R55") (pin "1") (pinfunction "1_1") (pintype "passive"))
    )
    (net (code "14") (name "/OUT8") (class "Default")
      (node (ref "IC4") (pin "28") (pinfunction "GPA7_28") (pintype "bidirectional"))
      (node (ref "OPTO8") (pin "4") (pinfunction "CT_4") (pintype "passive"))
      (node (ref "R56") (pin "1") (pinfunction "1_1") (pintype "passive"))
    )
    (net (code "15") (name "/OUT9") (class "Default")
      (node (ref "IC4") (pin "1") (pinfunction "GPB0_1") (pintype "bidirectional"))
      (node (ref "OPTO9") (pin "4") (pinfunction "CT_4") (pintype "passive"))
      (node (ref "R57") (pin "1") (pinfunction "1_1") (pintype "passive"))
    )
    (net (code "16") (name "/OUT10") (class "Default")
      (node (ref "IC4") (pin "2") (pinfunction "GPB1_2") (pintype "bidirectional"))
      (node (ref "OPTO10") (pin "4") (pinfunction "CT_4") (pintype "passive"))
      (node (ref "R58") (pin "1") (pinfunction "1_1") (pintype "passive"))
    )
    (net (code "17") (name "/OUT11") (class "Default")
      (node (ref "IC4") (pin "3") (pinfunction "GPB2_3") (pintype "bidirectional"))
      (node (ref "OPTO11") (pin "4") (pinfunction "CT_4") (pintype "passive"))
      (node (ref "R59") (pin "1") (pinfunction "1_1") (pintype "passive"))
    )
    (net (code "18") (name "/OUT12") (class "Default")
      (node (ref "IC4") (pin "4") (pinfunction "GPB3_4") (pintype "bidirectional"))
      (node (ref "OPTO12") (pin "4") (pinfunction "CT_4") (pintype "passive"))
      (node (ref "R60") (pin "1") (pinfunction "1_1") (pintype "passive"))
    )
    (net (code "19") (name "/OUT13") (class "Default")
      (node (ref "IC4") (pin "5") (pinfunction "GPB4_5") (pintype "bidirectional"))
      (node (ref "OPTO13") (pin "4") (pinfunction "CT_4") (pintype "passive"))
      (node (ref "R61") (pin "1") (pinfunction "1_1") (pintype "passive"))
    )
    (net (code "20") (name "/OUT14") (class "Default")
      (node (ref "IC4") (pin "6") (pinfunction "GPB5_6") (pintype "bidirectional"))
      (node (ref "OPTO14") (pin "4") (pinfunction "CT_4") (pintype "passive"))
      (node (ref "R62") (pin "1") (pinfunction "1_1") (pintype "passive"))
    )
    (net (code "21") (name "/OUT15") (class "Default")
      (node (ref "IC4") (pin "7") (pinfunction "GPB6_7") (pintype "bidirectional"))
      (node (ref "OPTO15") (pin "4") (pinfunction "CT_4") (pintype "passive"))
      (node (ref "R63") (pin "1") (pinfunction "1_1") (pintype "passive"))
    )
    (net (code "22") (name "/OUT16") (class "Default")
      (node (ref "IC4") (pin "8") (pinfunction "GPB7_8") (pintype "bidirectional"))
      (node (ref "OPTO16") (pin "4") (pinfunction "CT_4") (pintype "passive"))
      (node (ref "R64") (pin "1") (pinfunction "1_1") (pintype "passive"))
    )
    (net (code "23") (name "/OUT17") (class "Default")
      (node (ref "IC1") (pin "21") (pinfunction "GPA0_21") (pintype "bidirectional"))
      (node (ref "OPTO17") (pin "4") (pinfunction "CT_4") (pintype "passive"))
      (node (ref "R65") (pin "1") (pinfunction "1_1") (pintype "passive"))
    )
    (net (code "24") (name "/OUT18") (class "Default")
      (node (ref "IC1") (pin "22") (pinfunction "GPA1_22") (pintype "bidirectional"))
      (node (ref "OPTO18") (pin "4") (pinfunction "CT_4") (pintype "passive"))
      (node (ref "R66") (pin "1") (pinfunction "1_1") (pintype "passive"))
    )
    (net (code "25") (name "/OUT19") (class "Default")
      (node (ref "IC1") (pin "23") (pinfunction "GPA2_23") (pintype "bidirectional"))
      (node (ref "OPTO19") (pin "4") (pinfunction "CT_4") (pintype "passive"))
      (node (ref "R67") (pin "1") (pinfunction "1_1") (pintype "passive"))
    )
    (net (code "26") (name "/OUT20") (class "Default")
      (node (ref "IC1") (pin "24") (pinfunction "GPA3_24") (pintype "bidirectional"))
      (node (ref "OPTO20") (pin "4") (pinfunction "CT_4") (pintype "passive"))
      (node (ref "R68") (pin "1") (pinfunction "1_1") (pintype "passive"))
    )
    (net (code "27") (name "/OUT21") (class "Default")
      (node (ref "IC1") (pin "25") (pinfunction "GPA4_25") (pintype "bidirectional"))
      (node (ref "OPTO21") (pin "4") (pinfunction "CT_4") (pintype "passive"))
      (node (ref "R69") (pin "1") (pinfunction "1_1") (pintype "passive"))
    )
    (net (code "28") (name "/OUT22") (class "Default")
      (node (ref "IC1") (pin "26") (pinfunction "GPA5_26") (pintype "bidirectional"))
      (node (ref "OPTO22") (pin "4") (pinfunction "CT_4") (pintype "passive"))
      (node (ref "R70") (pin "1") (pinfunction "1_1") (pintype "passive"))
    )
    (net (code "29") (name "/OUT23") (class "Default")
      (node (ref "IC1") (pin "27") (pinfunction "GPA6_27") (pintype "bidirectional"))
      (node (ref "OPTO23") (pin "4") (pinfunction "CT_4") (pintype "passive"))
      (node (ref "R71") (pin "1") (pinfunction "1_1") (pintype "passive"))
    )
    (net (code "30") (name "/OUT24") (class "Default")
      (node (ref "IC1") (pin "28") (pinfunction "GPA7_28") (pintype "bidirectional"))
      (node (ref "OPTO24") (pin "4") (pinfunction "CT_4") (pintype "passive"))
      (node (ref "R72") (pin "1") (pinfunction "1_1") (pintype "passive"))
    )
    (net (code "31") (name "/OUT25") (class "Default")
      (node (ref "IC1") (pin "1") (pinfunction "GPB0_1") (pintype "bidirectional"))
      (node (ref "OPTO25") (pin "4") (pinfunction "CT_4") (pintype "passive"))
      (node (ref "R73") (pin "1") (pinfunction "1_1") (pintype "passive"))
    )
    (net (code "32") (name "/OUT26") (class "Default")
      (node (ref "IC1") (pin "2") (pinfunction "GPB1_2") (pintype "bidirectional"))
      (node (ref "OPTO26") (pin "4") (pinfunction "CT_4") (pintype "passive"))
      (node (ref "R74") (pin "1") (pinfunction "1_1") (pintype "passive"))
    )
    (net (code "33") (name "/OUT27") (class "Default")
      (node (ref "IC1") (pin "3") (pinfunction "GPB2_3") (pintype "bidirectional"))
      (node (ref "OPTO27") (pin "4") (pinfunction "CT_4") (pintype "passive"))
      (node (ref "R75") (pin "1") (pinfunction "1_1") (pintype "passive"))
    )
    (net (code "34") (name "/OUT28") (class "Default")
      (node (ref "IC1") (pin "4") (pinfunction "GPB3_4") (pintype "bidirectional"))
      (node (ref "OPTO28") (pin "4") (pinfunction "CT_4") (pintype "passive"))
      (node (ref "R76") (pin "1") (pinfunction "1_1") (pintype "passive"))
    )
    (net (code "35") (name "/OUT29") (class "Default")
      (node (ref "IC1") (pin "5") (pinfunction "GPB4_5") (pintype "bidirectional"))
      (node (ref "OPTO29") (pin "4") (pinfunction "CT_4") (pintype "passive"))
      (node (ref "R77") (pin "1") (pinfunction "1_1") (pintype "passive"))
    )
    (net (code "36") (name "/OUT30") (class "Default")
      (node (ref "IC1") (pin "6") (pinfunction "GPB5_6") (pintype "bidirectional"))
      (node (ref "OPTO30") (pin "4") (pinfunction "CT_4") (pintype "passive"))
      (node (ref "R78") (pin "1") (pinfunction "1_1") (pintype "passive"))
    )
    (net (code "37") (name "/OUT31") (class "Default")
      (node (ref "IC1") (pin "7") (pinfunction "GPB6_7") (pintype "bidirectional"))
      (node (ref "OPTO31") (pin "4") (pinfunction "CT_4") (pintype "passive"))
      (node (ref "R79") (pin "1") (pinfunction "1_1") (pintype "passive"))
    )
    (net (code "38") (name "/OUT32") (class "Default")
      (node (ref "IC1") (pin "8") (pinfunction "GPB7_8") (pintype "bidirectional"))
      (node (ref "OPTO32") (pin "4") (pinfunction "CT_4") (pintype "passive"))
      (node (ref "R80") (pin "1") (pinfunction "1_1") (pintype "passive"))
    )
    (net (code "39") (name "/OUT33") (class "Default")
      (node (ref "IC5") (pin "21") (pinfunction "GPA0_21") (pintype "bidirectional"))
      (node (ref "OPTO33") (pin "4") (pinfunction "CT_4") (pintype "passive"))
      (node (ref "R81") (pin "1") (pinfunction "1_1") (pintype "passive"))
    )
    (net (code "40") (name "/OUT34") (class "Default")
      (node (ref "IC5") (pin "22") (pinfunction "GPA1_22") (pintype "bidirectional"))
      (node (ref "OPTO34") (pin "4") (pinfunction "CT_4") (pintype "passive"))
      (node (ref "R82") (pin "1") (pinfunction "1_1") (pintype "passive"))
    )
    (net (code "41") (name "/OUT35") (class "Default")
      (node (ref "IC5") (pin "23") (pinfunction "GPA2_23") (pintype "bidirectional"))
      (node (ref "OPTO35") (pin "4") (pinfunction "CT_4") (pintype "passive"))
      (node (ref "R83") (pin "1") (pinfunction "1_1") (pintype "passive"))
    )
    (net (code "42") (name "/OUT36") (class "Default")
      (node (ref "IC5") (pin "24") (pinfunction "GPA3_24") (pintype "bidirectional"))
      (node (ref "OPTO36") (pin "4") (pinfunction "CT_4") (pintype "passive"))
      (node (ref "R84") (pin "1") (pinfunction "1_1") (pintype "passive"))
    )
    (net (code "43") (name "/OUT37") (class "Default")
      (node (ref "IC5") (pin "25") (pinfunction "GPA4_25") (pintype "bidirectional"))
      (node (ref "OPTO37") (pin "4") (pinfunction "CT_4") (pintype "passive"))
      (node (ref "R85") (pin "1") (pinfunction "1_1") (pintype "passive"))
    )
    (net (code "44") (name "/OUT38") (class "Default")
      (node (ref "IC5") (pin "26") (pinfunction "GPA5_26") (pintype "bidirectional"))
      (node (ref "OPTO38") (pin "4") (pinfunction "CT_4") (pintype "passive"))
      (node (ref "R86") (pin "1") (pinfunction "1_1") (pintype "passive"))
    )
    (net (code "45") (name "/OUT39") (class "Default")
      (node (ref "IC5") (pin "27") (pinfunction "GPA6_27") (pintype "bidirectional"))
      (node (ref "OPTO39") (pin "4") (pinfunction "CT_4") (pintype "passive"))
      (node (ref "R87") (pin "1") (pinfunction "1_1") (pintype "passive"))
    )
    (net (code "46") (name "/OUT40") (class "Default")
      (node (ref "IC5") (pin "28") (pinfunction "GPA7_28") (pintype "bidirectional"))
      (node (ref "OPTO40") (pin "4") (pinfunction "CT_4") (pintype "passive"))
      (node (ref "R88") (pin "1") (pinfunction "1_1") (pintype "passive"))
    )
    (net (code "47") (name "/OUT41") (class "Default")
      (node (ref "IC5") (pin "1") (pinfunction "GPB0_1") (pintype "bidirectional"))
      (node (ref "OPTO41") (pin "4") (pinfunction "CT_4") (pintype "passive"))
      (node (ref "R89") (pin "1") (pinfunction "1_1") (pintype "passive"))
    )
    (net (code "48") (name "/OUT42") (class "Default")
      (node (ref "IC5") (pin "2") (pinfunction "GPB1_2") (pintype "bidirectional"))
      (node (ref "OPTO42") (pin "4") (pinfunction "CT_4") (pintype "passive"))
      (node (ref "R90") (pin "1") (pinfunction "1_1") (pintype "passive"))
    )
    (net (code "49") (name "/OUT43") (class "Default")
      (node (ref "IC5") (pin "3") (pinfunction "GPB2_3") (pintype "bidirectional"))
      (node (ref "OPTO43") (pin "4") (pinfunction "CT_4") (pintype "passive"))
      (node (ref "R91") (pin "1") (pinfunction "1_1") (pintype "passive"))
    )
    (net (code "50") (name "/OUT44") (class "Default")
      (node (ref "IC5") (pin "4") (pinfunction "GPB3_4") (pintype "bidirectional"))
      (node (ref "OPTO44") (pin "4") (pinfunction "CT_4") (pintype "passive"))
      (node (ref "R92") (pin "1") (pinfunction "1_1") (pintype "passive"))
    )
    (net (code "51") (name "/OUT45") (class "Default")
      (node (ref "IC5") (pin "5") (pinfunction "GPB4_5") (pintype "bidirectional"))
      (node (ref "OPTO45") (pin "4") (pinfunction "CT_4") (pintype "passive"))
      (node (ref "R93") (pin "1") (pinfunction "1_1") (pintype "passive"))
    )
    (net (code "52") (name "/OUT46") (class "Default")
      (node (ref "IC5") (pin "6") (pinfunction "GPB5_6") (pintype "bidirectional"))
      (node (ref "OPTO46") (pin "4") (pinfunction "CT_4") (pintype "passive"))
      (node (ref "R94") (pin "1") (pinfunction "1_1") (pintype "passive"))
    )
    (net (code "53") (name "/OUT47") (class "Default")
      (node (ref "IC5") (pin "7") (pinfunction "GPB6_7") (pintype "bidirectional"))
      (node (ref "OPTO47") (pin "4") (pinfunction "CT_4") (pintype "passive"))
      (node (ref "R95") (pin "1") (pinfunction "1_1") (pintype "passive"))
    )
    (net (code "54") (name "/OUT48") (class "Default")
      (node (ref "IC5") (pin "8") (pinfunction "GPB7_8") (pintype "bidirectional"))
      (node (ref "OPTO48") (pin "4") (pinfunction "CT_4") (pintype "passive"))
      (node (ref "R96") (pin "1") (pinfunction "1_1") (pintype "passive"))
    )
    (net (code "55") (name "/P1") (class "Default")
      (node (ref "HEADER-29P1") (pin "1") (pinfunction "1_1") (pintype "bidirectional"))
      (node (ref "R1") (pin "1") (pinfunction "1_1") (pintype "passive"))
    )
    (net (code "56") (name "/P2") (class "Default")
      (node (ref "HEADER-29P1") (pin "2") (pinfunction "2_2") (pintype "bidirectional"))
      (node (ref "R2") (pin "1") (pinfunction "1_1") (pintype "passive"))
    )
    (net (code "57") (name "/P3") (class "Default")
      (node (ref "HEADER-29P1") (pin "3") (pinfunction "3_3") (pintype "bidirectional"))
      (node (ref "R3") (pin "1") (pinfunction "1_1") (pintype "passive"))
    )
    (net (code "58") (name "/P4") (class "Default")
      (node (ref "HEADER-29P1") (pin "4") (pinfunction "4_4") (pintype "bidirectional"))
      (node (ref "R4") (pin "1") (pinfunction "1_1") (pintype "passive"))
    )
    (net (code "59") (name "/P5") (class "Default")
      (node (ref "HEADER-29P1") (pin "5") (pinfunction "5_5") (pintype "bidirectional"))
      (node (ref "R5") (pin "1") (pinfunction "1_1") (pintype "passive"))
    )
    (net (code "60") (name "/P6") (class "Default")
      (node (ref "HEADER-29P1") (pin "6") (pinfunction "6_6") (pintype "bidirectional"))
      (node (ref "R6") (pin "1") (pinfunction "1_1") (pintype "passive"))
    )
    (net (code "61") (name "/P7") (class "Default")
      (node (ref "HEADER-29P1") (pin "7") (pinfunction "7_7") (pintype "bidirectional"))
      (node (ref "R7") (pin "1") (pinfunction "1_1") (pintype "passive"))
    )
    (net (code "62") (name "/P8") (class "Default")
      (node (ref "HEADER-29P1") (pin "8") (pinfunction "8_8") (pintype "bidirectional"))
      (node (ref "R8") (pin "1") (pinfunction "1_1") (pintype "passive"))
    )
    (net (code "63") (name "/P9") (class "Default")
      (node (ref "HEADER-29P1") (pin "9") (pinfunction "9_9") (pintype "bidirectional"))
      (node (ref "R9") (pin "1") (pinfunction "1_1") (pintype "passive"))
    )
    (net (code "64") (name "/P10") (class "Default")
      (node (ref "HEADER-29P1") (pin "10") (pinfunction "10_10") (pintype "bidirectional"))
      (node (ref "R10") (pin "1") (pinfunction "1_1") (pintype "passive"))
    )
    (net (code "65") (name "/P11") (class "Default")
      (node (ref "HEADER-29P1") (pin "11") (pinfunction "11_11") (pintype "bidirectional"))
      (node (ref "R11") (pin "1") (pinfunction "1_1") (pintype "passive"))
    )
    (net (code "66") (name "/P12") (class "Default")
      (node (ref "HEADER-29P1") (pin "12") (pinfunction "12_12") (pintype "bidirectional"))
      (node (ref "R12") (pin "1") (pinfunction "1_1") (pintype "passive"))
    )
    (net (code "67") (name "/P13") (class "Default")
      (node (ref "HEADER-29P1") (pin "13") (pinfunction "13_13") (pintype "bidirectional"))
      (node (ref "R13") (pin "1") (pinfunction "1_1") (pintype "passive"))
    )
    (net (code "68") (name "/P14") (class "Default")
      (node (ref "HEADER-29P1") (pin "14") (pinfunction "14_14") (pintype "bidirectional"))
      (node (ref "R14") (pin "1") (pinfunction "1_1") (pintype "passive"))
    )
    (net (code "69") (name "/P15") (class "Default")
      (node (ref "HEADER-29P1") (pin "15") (pinfunction "15_15") (pintype "bidirectional"))
      (node (ref "R15") (pin "1") (pinfunction "1_1") (pintype "passive"))
    )
    (net (code "70") (name "/P16") (class "Default")
      (node (ref "HEADER-29P1") (pin "16") (pinfunction "16_16") (pintype "bidirectional"))
      (node (ref "R16") (pin "1") (pinfunction "1_1") (pintype "passive"))
    )
    (net (code "71") (name "/P17") (class "Default")
      (node (ref "HEADER-29P1") (pin "17") (pinfunction "17_17") (pintype "bidirectional"))
      (node (ref "R17") (pin "1") (pinfunction "1_1") (pintype "passive"))
    )
    (net (code "72") (name "/P18") (class "Default")
      (node (ref "HEADER-29P1") (pin "18") (pinfunction "18_18") (pintype "bidirectional"))
      (node (ref "R18") (pin "1") (pinfunction "1_1") (pintype "passive"))
    )
    (net (code "73") (name "/P19") (class "Default")
      (node (ref "HEADER-29P1") (pin "19") (pinfunction "19_19") (pintype "bidirectional"))
      (node (ref "R19") (pin "1") (pinfunction "1_1") (pintype "passive"))
    )
    (net (code "74") (name "/P20") (class "Default")
      (node (ref "HEADER-29P1") (pin "20") (pinfunction "20_20") (pintype "bidirectional"))
      (node (ref "R20") (pin "1") (pinfunction "1_1") (pintype "passive"))
    )
    (net (code "75") (name "/P21") (class "Default")
      (node (ref "HEADER-29P1") (pin "21") (pinfunction "21_21") (pintype "bidirectional"))
      (node (ref "R21") (pin "1") (pinfunction "1_1") (pintype "passive"))
    )
    (net (code "76") (name "/P22") (class "Default")
      (node (ref "HEADER-29P1") (pin "22") (pinfunction "22_22") (pintype "bidirectional"))
      (node (ref "R22") (pin "1") (pinfunction "1_1") (pintype "passive"))
    )
    (net (code "77") (name "/P23") (class "Default")
      (node (ref "HEADER-29P1") (pin "23") (pinfunction "23_23") (pintype "bidirectional"))
      (node (ref "R23") (pin "1") (pinfunction "1_1") (pintype "passive"))
    )
    (net (code "78") (name "/P24") (class "Default")
      (node (ref "HEADER-29P1") (pin "24") (pinfunction "24_24") (pintype "bidirectional"))
      (node (ref "R24") (pin "1") (pinfunction "1_1") (pintype "passive"))
    )
    (net (code "79") (name "/P25") (class "Default")
      (node (ref "HEADER-29P1") (pin "25") (pinfunction "25_25") (pintype "bidirectional"))
      (node (ref "R25") (pin "1") (pinfunction "1_1") (pintype "passive"))
    )
    (net (code "80") (name "/P26") (class "Default")
      (node (ref "HEADER-29P1") (pin "26") (pinfunction "26_26") (pintype "bidirectional"))
      (node (ref "R26") (pin "1") (pinfunction "1_1") (pintype "passive"))
    )
    (net (code "81") (name "/P27") (class "Default")
      (node (ref "HEADER-29P1") (pin "27") (pinfunction "27_27") (pintype "bidirectional"))
      (node (ref "R27") (pin "1") (pinfunction "1_1") (pintype "passive"))
    )
    (net (code "82") (name "/P28") (class "Default")
      (node (ref "HEADER-29P1") (pin "28") (pinfunction "28_28") (pintype "bidirectional"))
      (node (ref "R28") (pin "1") (pinfunction "1_1") (pintype "passive"))
    )
    (net (code "83") (name "/P29") (class "Default")
      (node (ref "HEADER-29P1") (pin "29") (pinfunction "29_29") (pintype "bidirectional"))
      (node (ref "R29") (pin "1") (pinfunction "1_1") (pintype "passive"))
    )
    (net (code "84") (name "/P30") (class "Default")
      (node (ref "HEADER-22P1") (pin "1") (pinfunction "1_1") (pintype "bidirectional"))
      (node (ref "R30") (pin "1") (pinfunction "1_1") (pintype "passive"))
    )
    (net (code "85") (name "/P31") (class "Default")
      (node (ref "HEADER-22P1") (pin "2") (pinfunction "2_2") (pintype "bidirectional"))
      (node (ref "R31") (pin "1") (pinfunction "1_1") (pintype "passive"))
    )
    (net (code "86") (name "/P32") (class "Default")
      (node (ref "HEADER-22P1") (pin "3") (pinfunction "3_3") (pintype "bidirectional"))
      (node (ref "R32") (pin "1") (pinfunction "1_1") (pintype "passive"))
    )
    (net (code "87") (name "/P33") (class "Default")
      (node (ref "HEADER-22P1") (pin "4") (pinfunction "4_4") (pintype "bidirectional"))
      (node (ref "R33") (pin "1") (pinfunction "1_1") (pintype "passive"))
    )
    (net (code "88") (name "/P34") (class "Default")
      (node (ref "HEADER-22P1") (pin "5") (pinfunction "5_5") (pintype "bidirectional"))
      (node (ref "R34") (pin "1") (pinfunction "1_1") (pintype "passive"))
    )
    (net (code "89") (name "/P35") (class "Default")
      (node (ref "HEADER-22P1") (pin "6") (pinfunction "6_6") (pintype "bidirectional"))
      (node (ref "R35") (pin "1") (pinfunction "1_1") (pintype "passive"))
    )
    (net (code "90") (name "/P36") (class "Default")
      (node (ref "HEADER-22P1") (pin "7") (pinfunction "7_7") (pintype "bidirectional"))
      (node (ref "R36") (pin "1") (pinfunction "1_1") (pintype "passive"))
    )
    (net (code "91") (name "/P37") (class "Default")
      (node (ref "HEADER-22P1") (pin "8") (pinfunction "8_8") (pintype "bidirectional"))
      (node (ref "R37") (pin "1") (pinfunction "1_1") (pintype "passive"))
    )
    (net (code "92") (name "/P38") (class "Default")
      (node (ref "HEADER-22P1") (pin "9") (pinfunction "9_9") (pintype "bidirectional"))
      (node (ref "R38") (pin "1") (pinfunction "1_1") (pintype "passive"))
    )
    (net (code "93") (name "/P39") (class "Default")
      (node (ref "HEADER-22P1") (pin "10") (pinfunction "10_10") (pintype "bidirectional"))
      (node (ref "R39") (pin "1") (pinfunction "1_1") (pintype "passive"))
    )
    (net (code "94") (name "/P40") (class "Default")
      (node (ref "HEADER-22P1") (pin "11") (pinfunction "11_11") (pintype "bidirectional"))
      (node (ref "R40") (pin "1") (pinfunction "1_1") (pintype "passive"))
    )
    (net (code "95") (name "/P41") (class "Default")
      (node (ref "HEADER-22P1") (pin "12") (pinfunction "12_12") (pintype "bidirectional"))
      (node (ref "R41") (pin "1") (pinfunction "1_1") (pintype "passive"))
    )
    (net (code "96") (name "/P42") (class "Default")
      (node (ref "HEADER-22P1") (pin "13") (pinfunction "13_13") (pintype "bidirectional"))
      (node (ref "R42") (pin "1") (pinfunction "1_1") (pintype "passive"))
    )
    (net (code "97") (name "/P43") (class "Default")
      (node (ref "HEADER-22P1") (pin "14") (pinfunction "14_14") (pintype "bidirectional"))
      (node (ref "R43") (pin "1") (pinfunction "1_1") (pintype "passive"))
    )
    (net (code "98") (name "/P44") (class "Default")
      (node (ref "HEADER-22P1") (pin "15") (pinfunction "15_15") (pintype "bidirectional"))
      (node (ref "R44") (pin "1") (pinfunction "1_1") (pintype "passive"))
    )
    (net (code "99") (name "/P45") (class "Default")
      (node (ref "HEADER-22P1") (pin "16") (pinfunction "16_16") (pintype "bidirectional"))
      (node (ref "R45") (pin "1") (pinfunction "1_1") (pintype "passive"))
    )
    (net (code "100") (name "/P46") (class "Default")
      (node (ref "HEADER-22P1") (pin "17") (pinfunction "17_17") (pintype "bidirectional"))
      (node (ref "R46") (pin "1") (pinfunction "1_1") (pintype "passive"))
    )
    (net (code "101") (name "/P47") (class "Default")
      (node (ref "HEADER-22P1") (pin "18") (pinfunction "18_18") (pintype "bidirectional"))
      (node (ref "R47") (pin "1") (pinfunction "1_1") (pintype "passive"))
    )
    (net (code "102") (name "/P48") (class "Default")
      (node (ref "HEADER-22P1") (pin "19") (pinfunction "19_19") (pintype "bidirectional"))
      (node (ref "R48") (pin "1") (pinfunction "1_1") (pintype "passive"))
    )
    (net (code "103") (name "/RESET") (class "Default")
      (node (ref "IC1") (pin "18") (pinfunction "~{RESET}_18") (pintype "input"))
      (node (ref "IC4") (pin "18") (pinfunction "~{RESET}_18") (pintype "input"))
      (node (ref "IC5") (pin "18") (pinfunction "~{RESET}_18") (pintype "input"))
      (node (ref "R103") (pin "2") (pinfunction "2_2") (pintype "passive"))
      (node (ref "R107") (pin "1") (pinfunction "1_1") (pintype "passive"))
      (node (ref "R111") (pin "2") (pinfunction "2_2") (pintype "passive"))
      (node (ref "S1") (pin "2") (pinfunction "S_2") (pintype "passive"))
    )
    (net (code "104") (name "/RESET1") (class "Default")
      (node (ref "S1") (pin "1") (pinfunction "P_1") (pintype "passive"))
      (node (ref "SV1") (pin "4") (pinfunction "4_4") (pintype "passive"))
    )
    (net (code "105") (name "/RX") (class "Default")
      (node (ref "SV1") (pin "7") (pinfunction "7_7") (pintype "passive"))
      (node (ref "TTL-RS1") (pin "RX") (pinfunction "RX_RX") (pintype "bidirectional"))
    )
    (net (code "106") (name "/SCL") (class "Default")
      (node (ref "IC1") (pin "12") (pinfunction "SCL_12") (pintype "input"))
      (node (ref "IC4") (pin "12") (pinfunction "SCL_12") (pintype "input"))
      (node (ref "IC5") (pin "12") (pinfunction "SCL_12") (pintype "input"))
      (node (ref "R101") (pin "1") (pinfunction "1_1") (pintype "passive"))
      (node (ref "R97") (pin "1") (pinfunction "1_1") (pintype "passive"))
      (node (ref "R99") (pin "1") (pinfunction "1_1") (pintype "passive"))
      (node (ref "SV1") (pin "2") (pinfunction "2_2") (pintype "passive"))
    )
    (net (code "107") (name "/SDA") (class "Default")
      (node (ref "IC1") (pin "13") (pinfunction "SDA_13") (pintype "bidirectional"))
      (node (ref "IC4") (pin "13") (pinfunction "SDA_13") (pintype "bidirectional"))
      (node (ref "IC5") (pin "13") (pinfunction "SDA_13") (pintype "bidirectional"))
      (node (ref "R100") (pin "1") (pinfunction "1_1") (pintype "passive"))
      (node (ref "R102") (pin "1") (pinfunction "1_1") (pintype "passive"))
      (node (ref "R98") (pin "1") (pinfunction "1_1") (pintype "passive"))
      (node (ref "SV1") (pin "3") (pinfunction "3_3") (pintype "passive"))
    )
    (net (code "108") (name "/TX") (class "Default")
      (node (ref "SV1") (pin "8") (pinfunction "8_8") (pintype "passive"))
      (node (ref "TTL-RS1") (pin "TX") (pinfunction "TX_TX") (pintype "bidirectional"))
    )
    (net (code "109") (name "GND") (class "Default")
      (node (ref "IC1") (pin "10") (pinfunction "VSS_10") (pintype "power_in"))
      (node (ref "IC4") (pin "10") (pinfunction "VSS_10") (pintype "power_in"))
      (node (ref "IC5") (pin "10") (pinfunction "VSS_10") (pintype "power_in"))
      (node (ref "JP2") (pin "2") (pinfunction "2_2") (pintype "passive"))
      (node (ref "JP2") (pin "4") (pinfunction "4_4") (pintype "passive"))
      (node (ref "JP2") (pin "6") (pinfunction "6_6") (pintype "passive"))
      (node (ref "JP2") (pin "8") (pinfunction "8_8") (pintype "passive"))
      (node (ref "OPTO1") (pin "3") (pinfunction "ET_3") (pintype "passive"))
      (node (ref "OPTO10") (pin "3") (pinfunction "ET_3") (pintype "passive"))
      (node (ref "OPTO11") (pin "3") (pinfunction "ET_3") (pintype "passive"))
      (node (ref "OPTO12") (pin "3") (pinfunction "ET_3") (pintype "passive"))
      (node (ref "OPTO13") (pin "3") (pinfunction "ET_3") (pintype "passive"))
      (node (ref "OPTO14") (pin "3") (pinfunction "ET_3") (pintype "passive"))
      (node (ref "OPTO15") (pin "3") (pinfunction "ET_3") (pintype "passive"))
      (node (ref "OPTO16") (pin "3") (pinfunction "ET_3") (pintype "passive"))
      (node (ref "OPTO17") (pin "3") (pinfunction "ET_3") (pintype "passive"))
      (node (ref "OPTO18") (pin "3") (pinfunction "ET_3") (pintype "passive"))
      (node (ref "OPTO19") (pin "3") (pinfunction "ET_3") (pintype "passive"))
      (node (ref "OPTO2") (pin "3") (pinfunction "ET_3") (pintype "passive"))
      (node (ref "OPTO20") (pin "3") (pinfunction "ET_3") (pintype "passive"))
      (node (ref "OPTO21") (pin "3") (pinfunction "ET_3") (pintype "passive"))
      (node (ref "OPTO22") (pin "3") (pinfunction "ET_3") (pintype "passive"))
      (node (ref "OPTO23") (pin "3") (pinfunction "ET_3") (pintype "passive"))
      (node (ref "OPTO24") (pin "3") (pinfunction "ET_3") (pintype "passive"))
      (node (ref "OPTO25") (pin "3") (pinfunction "ET_3") (pintype "passive"))
      (node (ref "OPTO26") (pin "3") (pinfunction "ET_3") (pintype "passive"))
      (node (ref "OPTO27") (pin "3") (pinfunction "ET_3") (pintype "passive"))
      (node (ref "OPTO28") (pin "3") (pinfunction "ET_3") (pintype "passive"))
      (node (ref "OPTO29") (pin "3") (pinfunction "ET_3") (pintype "passive"))
      (node (ref "OPTO3") (pin "3") (pinfunction "ET_3") (pintype "passive"))
      (node (ref "OPTO30") (pin "3") (pinfunction "ET_3") (pintype "passive"))
      (node (ref "OPTO31") (pin "3") (pinfunction "ET_3") (pintype "passive"))
      (node (ref "OPTO32") (pin "3") (pinfunction "ET_3") (pintype "passive"))
      (node (ref "OPTO33") (pin "3") (pinfunction "ET_3") (pintype "passive"))
      (node (ref "OPTO34") (pin "3") (pinfunction "ET_3") (pintype "passive"))
      (node (ref "OPTO35") (pin "3") (pinfunction "ET_3") (pintype "passive"))
      (node (ref "OPTO36") (pin "3") (pinfunction "ET_3") (pintype "passive"))
      (node (ref "OPTO37") (pin "3") (pinfunction "ET_3") (pintype "passive"))
      (node (ref "OPTO38") (pin "3") (pinfunction "ET_3") (pintype "passive"))
      (node (ref "OPTO39") (pin "3") (pinfunction "ET_3") (pintype "passive"))
      (node (ref "OPTO4") (pin "3") (pinfunction "ET_3") (pintype "passive"))
      (node (ref "OPTO40") (pin "3") (pinfunction "ET_3") (pintype "passive"))
      (node (ref "OPTO41") (pin "3") (pinfunction "ET_3") (pintype "passive"))
      (node (ref "OPTO42") (pin "3") (pinfunction "ET_3") (pintype "passive"))
      (node (ref "OPTO43") (pin "3") (pinfunction "ET_3") (pintype "passive"))
      (node (ref "OPTO44") (pin "3") (pinfunction "ET_3") (pintype "passive"))
      (node (ref "OPTO45") (pin "3") (pinfunction "ET_3") (pintype "passive"))
      (node (ref "OPTO46") (pin "3") (pinfunction "ET_3") (pintype "passive"))
      (node (ref "OPTO47") (pin "3") (pinfunction "ET_3") (pintype "passive"))
      (node (ref "OPTO48") (pin "3") (pinfunction "ET_3") (pintype "passive"))
      (node (ref "OPTO5") (pin "3") (pinfunction "ET_3") (pintype "passive"))
      (node (ref "OPTO6") (pin "3") (pinfunction "ET_3") (pintype "passive"))
      (node (ref "OPTO7") (pin "3") (pinfunction "ET_3") (pintype "passive"))
      (node (ref "OPTO8") (pin "3") (pinfunction "ET_3") (pintype "passive"))
      (node (ref "OPTO9") (pin "3") (pinfunction "ET_3") (pintype "passive"))
      (node (ref "Q1") (pin "2") (pinfunction "E_2") (pintype "passive"))
      (node (ref "R104") (pin "1") (pinfunction "1_1") (pintype "passive"))
      (node (ref "R105") (pin "1") (pinfunction "1_1") (pintype "passive"))
      (node (ref "R106") (pin "1") (pinfunction "1_1") (pintype "passive"))
      (node (ref "R109") (pin "1") (pinfunction "1_1") (pintype "passive"))
      (node (ref "R110") (pin "1") (pinfunction "1_1") (pintype "passive"))
      (node (ref "R112") (pin "1") (pinfunction "1_1") (pintype "passive"))
      (node (ref "R114") (pin "1") (pinfunction "1_1") (pintype "passive"))
      (node (ref "SV1") (pin "10") (pinfunction "10_10") (pintype "passive"))
      (node (ref "TTL-RS1") (pin "GND") (pinfunction "GND_GND") (pintype "bidirectional"))
      (node (ref "U49") (pin "2") (pinfunction "C_2") (pintype "passive"))
    )
    (net (code "110") (name "Net-(D2-K)") (class "Default")
      (node (ref "D2") (pin "C") (pinfunction "K_C") (pintype "passive"))
      (node (ref "LED1") (pin "+") (pinfunction "+_+") (pintype "passive"))
    )
    (net (code "111") (name "Net-(D2-PadA)") (class "Default")
      (node (ref "D2") (pin "A") (pinfunction "A_A") (pintype "passive"))
      (node (ref "R1") (pin "2") (pinfunction "2_2") (pintype "passive"))
    )
    (net (code "112") (name "Net-(D3-K)") (class "Default")
      (node (ref "D3") (pin "C") (pinfunction "K_C") (pintype "passive"))
      (node (ref "LED2") (pin "+") (pinfunction "+_+") (pintype "passive"))
    )
    (net (code "113") (name "Net-(D3-PadA)") (class "Default")
      (node (ref "D3") (pin "A") (pinfunction "A_A") (pintype "passive"))
      (node (ref "R2") (pin "2") (pinfunction "2_2") (pintype "passive"))
    )
    (net (code "114") (name "Net-(D4-K)") (class "Default")
      (node (ref "D4") (pin "C") (pinfunction "K_C") (pintype "passive"))
      (node (ref "LED3") (pin "+") (pinfunction "+_+") (pintype "passive"))
    )
    (net (code "115") (name "Net-(D4-PadA)") (class "Default")
      (node (ref "D4") (pin "A") (pinfunction "A_A") (pintype "passive"))
      (node (ref "R3") (pin "2") (pinfunction "2_2") (pintype "passive"))
    )
    (net (code "116") (name "Net-(D5-K)") (class "Default")
      (node (ref "D5") (pin "C") (pinfunction "K_C") (pintype "passive"))
      (node (ref "LED4") (pin "+") (pinfunction "+_+") (pintype "passive"))
    )
    (net (code "117") (name "Net-(D5-PadA)") (class "Default")
      (node (ref "D5") (pin "A") (pinfunction "A_A") (pintype "passive"))
      (node (ref "R4") (pin "2") (pinfunction "2_2") (pintype "passive"))
    )
    (net (code "118") (name "Net-(D6-K)") (class "Default")
      (node (ref "D6") (pin "C") (pinfunction "K_C") (pintype "passive"))
      (node (ref "LED5") (pin "+") (pinfunction "+_+") (pintype "passive"))
    )
    (net (code "119") (name "Net-(D6-PadA)") (class "Default")
      (node (ref "D6") (pin "A") (pinfunction "A_A") (pintype "passive"))
      (node (ref "R5") (pin "2") (pinfunction "2_2") (pintype "passive"))
    )
    (net (code "120") (name "Net-(D7-K)") (class "Default")
      (node (ref "D7") (pin "C") (pinfunction "K_C") (pintype "passive"))
      (node (ref "LED6") (pin "+") (pinfunction "+_+") (pintype "passive"))
    )
    (net (code "121") (name "Net-(D7-PadA)") (class "Default")
      (node (ref "D7") (pin "A") (pinfunction "A_A") (pintype "passive"))
      (node (ref "R6") (pin "2") (pinfunction "2_2") (pintype "passive"))
    )
    (net (code "122") (name "Net-(D8-K)") (class "Default")
      (node (ref "D8") (pin "C") (pinfunction "K_C") (pintype "passive"))
      (node (ref "LED7") (pin "+") (pinfunction "+_+") (pintype "passive"))
    )
    (net (code "123") (name "Net-(D8-PadA)") (class "Default")
      (node (ref "D8") (pin "A") (pinfunction "A_A") (pintype "passive"))
      (node (ref "R7") (pin "2") (pinfunction "2_2") (pintype "passive"))
    )
    (net (code "124") (name "Net-(D9-K)") (class "Default")
      (node (ref "D9") (pin "C") (pinfunction "K_C") (pintype "passive"))
      (node (ref "LED8") (pin "+") (pinfunction "+_+") (pintype "passive"))
    )
    (net (code "125") (name "Net-(D9-PadA)") (class "Default")
      (node (ref "D9") (pin "A") (pinfunction "A_A") (pintype "passive"))
      (node (ref "R8") (pin "2") (pinfunction "2_2") (pintype "passive"))
    )
    (net (code "126") (name "Net-(D10-K)") (class "Default")
      (node (ref "D10") (pin "C") (pinfunction "K_C") (pintype "passive"))
      (node (ref "LED9") (pin "+") (pinfunction "+_+") (pintype "passive"))
    )
    (net (code "127") (name "Net-(D10-PadA)") (class "Default")
      (node (ref "D10") (pin "A") (pinfunction "A_A") (pintype "passive"))
      (node (ref "R9") (pin "2") (pinfunction "2_2") (pintype "passive"))
    )
    (net (code "128") (name "Net-(D11-K)") (class "Default")
      (node (ref "D11") (pin "C") (pinfunction "K_C") (pintype "passive"))
      (node (ref "LED10") (pin "+") (pinfunction "+_+") (pintype "passive"))
    )
    (net (code "129") (name "Net-(D11-PadA)") (class "Default")
      (node (ref "D11") (pin "A") (pinfunction "A_A") (pintype "passive"))
      (node (ref "R10") (pin "2") (pinfunction "2_2") (pintype "passive"))
    )
    (net (code "130") (name "Net-(D12-K)") (class "Default")
      (node (ref "D12") (pin "C") (pinfunction "K_C") (pintype "passive"))
      (node (ref "LED11") (pin "+") (pinfunction "+_+") (pintype "passive"))
    )
    (net (code "131") (name "Net-(D12-PadA)") (class "Default")
      (node (ref "D12") (pin "A") (pinfunction "A_A") (pintype "passive"))
      (node (ref "R11") (pin "2") (pinfunction "2_2") (pintype "passive"))
    )
    (net (code "132") (name "Net-(D13-K)") (class "Default")
      (node (ref "D13") (pin "C") (pinfunction "K_C") (pintype "passive"))
      (node (ref "LED12") (pin "+") (pinfunction "+_+") (pintype "passive"))
    )
    (net (code "133") (name "Net-(D13-PadA)") (class "Default")
      (node (ref "D13") (pin "A") (pinfunction "A_A") (pintype "passive"))
      (node (ref "R12") (pin "2") (pinfunction "2_2") (pintype "passive"))
    )
    (net (code "134") (name "Net-(D14-K)") (class "Default")
      (node (ref "D14") (pin "C") (pinfunction "K_C") (pintype "passive"))
      (node (ref "LED13") (pin "+") (pinfunction "+_+") (pintype "passive"))
    )
    (net (code "135") (name "Net-(D14-PadA)") (class "Default")
      (node (ref "D14") (pin "A") (pinfunction "A_A") (pintype "passive"))
      (node (ref "R13") (pin "2") (pinfunction "2_2") (pintype "passive"))
    )
    (net (code "136") (name "Net-(D15-K)") (class "Default")
      (node (ref "D15") (pin "C") (pinfunction "K_C") (pintype "passive"))
      (node (ref "LED14") (pin "+") (pinfunction "+_+") (pintype "passive"))
    )
    (net (code "137") (name "Net-(D15-PadA)") (class "Default")
      (node (ref "D15") (pin "A") (pinfunction "A_A") (pintype "passive"))
      (node (ref "R14") (pin "2") (pinfunction "2_2") (pintype "passive"))
    )
    (net (code "138") (name "Net-(D16-K)") (class "Default")
      (node (ref "D16") (pin "C") (pinfunction "K_C") (pintype "passive"))
      (node (ref "LED15") (pin "+") (pinfunction "+_+") (pintype "passive"))
    )
    (net (code "139") (name "Net-(D16-PadA)") (class "Default")
      (node (ref "D16") (pin "A") (pinfunction "A_A") (pintype "passive"))
      (node (ref "R15") (pin "2") (pinfunction "2_2") (pintype "passive"))
    )
    (net (code "140") (name "Net-(D17-K)") (class "Default")
      (node (ref "D17") (pin "C") (pinfunction "K_C") (pintype "passive"))
      (node (ref "LED16") (pin "+") (pinfunction "+_+") (pintype "passive"))
    )
    (net (code "141") (name "Net-(D17-PadA)") (class "Default")
      (node (ref "D17") (pin "A") (pinfunction "A_A") (pintype "passive"))
      (node (ref "R16") (pin "2") (pinfunction "2_2") (pintype "passive"))
    )
    (net (code "142") (name "Net-(D18-K)") (class "Default")
      (node (ref "D18") (pin "C") (pinfunction "K_C") (pintype "passive"))
      (node (ref "LED17") (pin "+") (pinfunction "+_+") (pintype "passive"))
    )
    (net (code "143") (name "Net-(D18-PadA)") (class "Default")
      (node (ref "D18") (pin "A") (pinfunction "A_A") (pintype "passive"))
      (node (ref "R17") (pin "2") (pinfunction "2_2") (pintype "passive"))
    )
    (net (code "144") (name "Net-(D19-K)") (class "Default")
      (node (ref "D19") (pin "C") (pinfunction "K_C") (pintype "passive"))
      (node (ref "LED18") (pin "+") (pinfunction "+_+") (pintype "passive"))
    )
    (net (code "145") (name "Net-(D19-PadA)") (class "Default")
      (node (ref "D19") (pin "A") (pinfunction "A_A") (pintype "passive"))
      (node (ref "R18") (pin "2") (pinfunction "2_2") (pintype "passive"))
    )
    (net (code "146") (name "Net-(D20-K)") (class "Default")
      (node (ref "D20") (pin "C") (pinfunction "K_C") (pintype "passive"))
      (node (ref "LED19") (pin "+") (pinfunction "+_+") (pintype "passive"))
    )
    (net (code "147") (name "Net-(D20-PadA)") (class "Default")
      (node (ref "D20") (pin "A") (pinfunction "A_A") (pintype "passive"))
      (node (ref "R19") (pin "2") (pinfunction "2_2") (pintype "passive"))
    )
    (net (code "148") (name "Net-(D21-K)") (class "Default")
      (node (ref "D21") (pin "C") (pinfunction "K_C") (pintype "passive"))
      (node (ref "LED20") (pin "+") (pinfunction "+_+") (pintype "passive"))
    )
    (net (code "149") (name "Net-(D21-PadA)") (class "Default")
      (node (ref "D21") (pin "A") (pinfunction "A_A") (pintype "passive"))
      (node (ref "R20") (pin "2") (pinfunction "2_2") (pintype "passive"))
    )
    (net (code "150") (name "Net-(D22-K)") (class "Default")
      (node (ref "D22") (pin "C") (pinfunction "K_C") (pintype "passive"))
      (node (ref "LED21") (pin "+") (pinfunction "+_+") (pintype "passive"))
    )
    (net (code "151") (name "Net-(D22-PadA)") (class "Default")
      (node (ref "D22") (pin "A") (pinfunction "A_A") (pintype "passive"))
      (node (ref "R21") (pin "2") (pinfunction "2_2") (pintype "passive"))
    )
    (net (code "152") (name "Net-(D23-K)") (class "Default")
      (node (ref "D23") (pin "C") (pinfunction "K_C") (pintype "passive"))
      (node (ref "LED22") (pin "+") (pinfunction "+_+") (pintype "passive"))
    )
    (net (code "153") (name "Net-(D23-PadA)") (class "Default")
      (node (ref "D23") (pin "A") (pinfunction "A_A") (pintype "passive"))
      (node (ref "R22") (pin "2") (pinfunction "2_2") (pintype "passive"))
    )
    (net (code "154") (name "Net-(D24-K)") (class "Default")
      (node (ref "D24") (pin "C") (pinfunction "K_C") (pintype "passive"))
      (node (ref "LED23") (pin "+") (pinfunction "+_+") (pintype "passive"))
    )
    (net (code "155") (name "Net-(D24-PadA)") (class "Default")
      (node (ref "D24") (pin "A") (pinfunction "A_A") (pintype "passive"))
      (node (ref "R23") (pin "2") (pinfunction "2_2") (pintype "passive"))
    )
    (net (code "156") (name "Net-(D25-K)") (class "Default")
      (node (ref "D25") (pin "C") (pinfunction "K_C") (pintype "passive"))
      (node (ref "LED24") (pin "+") (pinfunction "+_+") (pintype "passive"))
    )
    (net (code "157") (name "Net-(D25-PadA)") (class "Default")
      (node (ref "D25") (pin "A") (pinfunction "A_A") (pintype "passive"))
      (node (ref "R24") (pin "2") (pinfunction "2_2") (pintype "passive"))
    )
    (net (code "158") (name "Net-(D26-K)") (class "Default")
      (node (ref "D26") (pin "C") (pinfunction "K_C") (pintype "passive"))
      (node (ref "LED25") (pin "+") (pinfunction "+_+") (pintype "passive"))
    )
    (net (code "159") (name "Net-(D26-PadA)") (class "Default")
      (node (ref "D26") (pin "A") (pinfunction "A_A") (pintype "passive"))
      (node (ref "R25") (pin "2") (pinfunction "2_2") (pintype "passive"))
    )
    (net (code "160") (name "Net-(D27-K)") (class "Default")
      (node (ref "D27") (pin "C") (pinfunction "K_C") (pintype "passive"))
      (node (ref "LED26") (pin "+") (pinfunction "+_+") (pintype "passive"))
    )
    (net (code "161") (name "Net-(D27-PadA)") (class "Default")
      (node (ref "D27") (pin "A") (pinfunction "A_A") (pintype "passive"))
      (node (ref "R26") (pin "2") (pinfunction "2_2") (pintype "passive"))
    )
    (net (code "162") (name "Net-(D28-K)") (class "Default")
      (node (ref "D28") (pin "C") (pinfunction "K_C") (pintype "passive"))
      (node (ref "LED27") (pin "+") (pinfunction "+_+") (pintype "passive"))
    )
    (net (code "163") (name "Net-(D28-PadA)") (class "Default")
      (node (ref "D28") (pin "A") (pinfunction "A_A") (pintype "passive"))
      (node (ref "R27") (pin "2") (pinfunction "2_2") (pintype "passive"))
    )
    (net (code "164") (name "Net-(D29-K)") (class "Default")
      (node (ref "D29") (pin "C") (pinfunction "K_C") (pintype "passive"))
      (node (ref "LED28") (pin "+") (pinfunction "+_+") (pintype "passive"))
    )
    (net (code "165") (name "Net-(D29-PadA)") (class "Default")
      (node (ref "D29") (pin "A") (pinfunction "A_A") (pintype "passive"))
      (node (ref "R28") (pin "2") (pinfunction "2_2") (pintype "passive"))
    )
    (net (code "166") (name "Net-(D30-K)") (class "Default")
      (node (ref "D30") (pin "C") (pinfunction "K_C") (pintype "passive"))
      (node (ref "LED29") (pin "+") (pinfunction "+_+") (pintype "passive"))
    )
    (net (code "167") (name "Net-(D30-PadA)") (class "Default")
      (node (ref "D30") (pin "A") (pinfunction "A_A") (pintype "passive"))
      (node (ref "R29") (pin "2") (pinfunction "2_2") (pintype "passive"))
    )
    (net (code "168") (name "Net-(D31-K)") (class "Default")
      (node (ref "D31") (pin "C") (pinfunction "K_C") (pintype "passive"))
      (node (ref "LED30") (pin "+") (pinfunction "+_+") (pintype "passive"))
    )
    (net (code "169") (name "Net-(D31-PadA)") (class "Default")
      (node (ref "D31") (pin "A") (pinfunction "A_A") (pintype "passive"))
      (node (ref "R30") (pin "2") (pinfunction "2_2") (pintype "passive"))
    )
    (net (code "170") (name "Net-(D32-K)") (class "Default")
      (node (ref "D32") (pin "C") (pinfunction "K_C") (pintype "passive"))
      (node (ref "LED31") (pin "+") (pinfunction "+_+") (pintype "passive"))
    )
    (net (code "171") (name "Net-(D32-PadA)") (class "Default")
      (node (ref "D32") (pin "A") (pinfunction "A_A") (pintype "passive"))
      (node (ref "R31") (pin "2") (pinfunction "2_2") (pintype "passive"))
    )
    (net (code "172") (name "Net-(D33-K)") (class "Default")
      (node (ref "D33") (pin "C") (pinfunction "K_C") (pintype "passive"))
      (node (ref "LED32") (pin "+") (pinfunction "+_+") (pintype "passive"))
    )
    (net (code "173") (name "Net-(D33-PadA)") (class "Default")
      (node (ref "D33") (pin "A") (pinfunction "A_A") (pintype "passive"))
      (node (ref "R32") (pin "2") (pinfunction "2_2") (pintype "passive"))
    )
    (net (code "174") (name "Net-(D34-K)") (class "Default")
      (node (ref "D34") (pin "C") (pinfunction "K_C") (pintype "passive"))
      (node (ref "LED33") (pin "+") (pinfunction "+_+") (pintype "passive"))
    )
    (net (code "175") (name "Net-(D34-PadA)") (class "Default")
      (node (ref "D34") (pin "A") (pinfunction "A_A") (pintype "passive"))
      (node (ref "R33") (pin "2") (pinfunction "2_2") (pintype "passive"))
    )
    (net (code "176") (name "Net-(D35-K)") (class "Default")
      (node (ref "D35") (pin "C") (pinfunction "K_C") (pintype "passive"))
      (node (ref "LED34") (pin "+") (pinfunction "+_+") (pintype "passive"))
    )
    (net (code "177") (name "Net-(D35-PadA)") (class "Default")
      (node (ref "D35") (pin "A") (pinfunction "A_A") (pintype "passive"))
      (node (ref "R34") (pin "2") (pinfunction "2_2") (pintype "passive"))
    )
    (net (code "178") (name "Net-(D36-K)") (class "Default")
      (node (ref "D36") (pin "C") (pinfunction "K_C") (pintype "passive"))
      (node (ref "LED35") (pin "+") (pinfunction "+_+") (pintype "passive"))
    )
    (net (code "179") (name "Net-(D36-PadA)") (class "Default")
      (node (ref "D36") (pin "A") (pinfunction "A_A") (pintype "passive"))
      (node (ref "R35") (pin "2") (pinfunction "2_2") (pintype "passive"))
    )
    (net (code "180") (name "Net-(D37-K)") (class "Default")
      (node (ref "D37") (pin "C") (pinfunction "K_C") (pintype "passive"))
      (node (ref "LED36") (pin "+") (pinfunction "+_+") (pintype "passive"))
    )
    (net (code "181") (name "Net-(D37-PadA)") (class "Default")
      (node (ref "D37") (pin "A") (pinfunction "A_A") (pintype "passive"))
      (node (ref "R36") (pin "2") (pinfunction "2_2") (pintype "passive"))
    )
    (net (code "182") (name "Net-(D38-K)") (class "Default")
      (node (ref "D38") (pin "C") (pinfunction "K_C") (pintype "passive"))
      (node (ref "LED37") (pin "+") (pinfunction "+_+") (pintype "passive"))
    )
    (net (code "183") (name "Net-(D38-PadA)") (class "Default")
      (node (ref "D38") (pin "A") (pinfunction "A_A") (pintype "passive"))
      (node (ref "R37") (pin "2") (pinfunction "2_2") (pintype "passive"))
    )
    (net (code "184") (name "Net-(D39-K)") (class "Default")
      (node (ref "D39") (pin "C") (pinfunction "K_C") (pintype "passive"))
      (node (ref "LED38") (pin "+") (pinfunction "+_+") (pintype "passive"))
    )
    (net (code "185") (name "Net-(D39-PadA)") (class "Default")
      (node (ref "D39") (pin "A") (pinfunction "A_A") (pintype "passive"))
      (node (ref "R38") (pin "2") (pinfunction "2_2") (pintype "passive"))
    )
    (net (code "186") (name "Net-(D40-K)") (class "Default")
      (node (ref "D40") (pin "C") (pinfunction "K_C") (pintype "passive"))
      (node (ref "LED39") (pin "+") (pinfunction "+_+") (pintype "passive"))
    )
    (net (code "187") (name "Net-(D40-PadA)") (class "Default")
      (node (ref "D40") (pin "A") (pinfunction "A_A") (pintype "passive"))
      (node (ref "R39") (pin "2") (pinfunction "2_2") (pintype "passive"))
    )
    (net (code "188") (name "Net-(D41-K)") (class "Default")
      (node (ref "D41") (pin "C") (pinfunction "K_C") (pintype "passive"))
      (node (ref "LED40") (pin "+") (pinfunction "+_+") (pintype "passive"))
    )
    (net (code "189") (name "Net-(D41-PadA)") (class "Default")
      (node (ref "D41") (pin "A") (pinfunction "A_A") (pintype "passive"))
      (node (ref "R40") (pin "2") (pinfunction "2_2") (pintype "passive"))
    )
    (net (code "190") (name "Net-(D42-K)") (class "Default")
      (node (ref "D42") (pin "C") (pinfunction "K_C") (pintype "passive"))
      (node (ref "LED41") (pin "+") (pinfunction "+_+") (pintype "passive"))
    )
    (net (code "191") (name "Net-(D42-PadA)") (class "Default")
      (node (ref "D42") (pin "A") (pinfunction "A_A") (pintype "passive"))
      (node (ref "R41") (pin "2") (pinfunction "2_2") (pintype "passive"))
    )
    (net (code "192") (name "Net-(D43-K)") (class "Default")
      (node (ref "D43") (pin "C") (pinfunction "K_C") (pintype "passive"))
      (node (ref "LED42") (pin "+") (pinfunction "+_+") (pintype "passive"))
    )
    (net (code "193") (name "Net-(D43-PadA)") (class "Default")
      (node (ref "D43") (pin "A") (pinfunction "A_A") (pintype "passive"))
      (node (ref "R42") (pin "2") (pinfunction "2_2") (pintype "passive"))
    )
    (net (code "194") (name "Net-(D44-K)") (class "Default")
      (node (ref "D44") (pin "C") (pinfunction "K_C") (pintype "passive"))
      (node (ref "LED43") (pin "+") (pinfunction "+_+") (pintype "passive"))
    )
    (net (code "195") (name "Net-(D44-PadA)") (class "Default")
      (node (ref "D44") (pin "A") (pinfunction "A_A") (pintype "passive"))
      (node (ref "R43") (pin "2") (pinfunction "2_2") (pintype "passive"))
    )
    (net (code "196") (name "Net-(D45-K)") (class "Default")
      (node (ref "D45") (pin "C") (pinfunction "K_C") (pintype "passive"))
      (node (ref "LED44") (pin "+") (pinfunction "+_+") (pintype "passive"))
    )
    (net (code "197") (name "Net-(D45-PadA)") (class "Default")
      (node (ref "D45") (pin "A") (pinfunction "A_A") (pintype "passive"))
      (node (ref "R44") (pin "2") (pinfunction "2_2") (pintype "passive"))
    )
    (net (code "198") (name "Net-(D46-K)") (class "Default")
      (node (ref "D46") (pin "C") (pinfunction "K_C") (pintype "passive"))
      (node (ref "LED45") (pin "+") (pinfunction "+_+") (pintype "passive"))
    )
    (net (code "199") (name "Net-(D46-PadA)") (class "Default")
      (node (ref "D46") (pin "A") (pinfunction "A_A") (pintype "passive"))
      (node (ref "R45") (pin "2") (pinfunction "2_2") (pintype "passive"))
    )
    (net (code "200") (name "Net-(D47-K)") (class "Default")
      (node (ref "D47") (pin "C") (pinfunction "K_C") (pintype "passive"))
      (node (ref "LED46") (pin "+") (pinfunction "+_+") (pintype "passive"))
    )
    (net (code "201") (name "Net-(D47-PadA)") (class "Default")
      (node (ref "D47") (pin "A") (pinfunction "A_A") (pintype "passive"))
      (node (ref "R46") (pin "2") (pinfunction "2_2") (pintype "passive"))
    )
    (net (code "202") (name "Net-(D48-K)") (class "Default")
      (node (ref "D48") (pin "C") (pinfunction "K_C") (pintype "passive"))
      (node (ref "LED47") (pin "+") (pinfunction "+_+") (pintype "passive"))
    )
    (net (code "203") (name "Net-(D48-PadA)") (class "Default")
      (node (ref "D48") (pin "A") (pinfunction "A_A") (pintype "passive"))
      (node (ref "R47") (pin "2") (pinfunction "2_2") (pintype "passive"))
    )
    (net (code "204") (name "Net-(D49-K)") (class "Default")
      (node (ref "D49") (pin "C") (pinfunction "K_C") (pintype "passive"))
      (node (ref "LED48") (pin "+") (pinfunction "+_+") (pintype "passive"))
    )
    (net (code "205") (name "Net-(D49-PadA)") (class "Default")
      (node (ref "D49") (pin "A") (pinfunction "A_A") (pintype "passive"))
      (node (ref "R48") (pin "2") (pinfunction "2_2") (pintype "passive"))
    )
    (net (code "206") (name "Net-(D146-Pad+)") (class "Default")
      (node (ref "D146") (pin "+") (pinfunction "+_+") (pintype "passive"))
      (node (ref "R115") (pin "1") (pinfunction "1_1") (pintype "passive"))
    )
    (net (code "207") (name "Net-(IC1-A0)") (class "Default")
      (node (ref "IC1") (pin "15") (pinfunction "A0_15") (pintype "input"))
      (node (ref "R108") (pin "2") (pinfunction "2_2") (pintype "passive"))
    )
    (net (code "208") (name "Net-(IC1-A1)") (class "Default")
      (node (ref "IC1") (pin "16") (pinfunction "A1_16") (pintype "input"))
      (node (ref "R109") (pin "2") (pinfunction "2_2") (pintype "passive"))
    )
    (net (code "209") (name "Net-(IC1-A2)") (class "Default")
      (node (ref "IC1") (pin "17") (pinfunction "A2_17") (pintype "input"))
      (node (ref "R110") (pin "2") (pinfunction "2_2") (pintype "passive"))
    )
    (net (code "210") (name "Net-(IC4-A0)") (class "Default")
      (node (ref "IC4") (pin "15") (pinfunction "A0_15") (pintype "input"))
      (node (ref "R106") (pin "2") (pinfunction "2_2") (pintype "passive"))
    )
    (net (code "211") (name "Net-(IC4-A1)") (class "Default")
      (node (ref "IC4") (pin "16") (pinfunction "A1_16") (pintype "input"))
      (node (ref "R105") (pin "2") (pinfunction "2_2") (pintype "passive"))
    )
    (net (code "212") (name "Net-(IC4-A2)") (class "Default")
      (node (ref "IC4") (pin "17") (pinfunction "A2_17") (pintype "input"))
      (node (ref "R104") (pin "2") (pinfunction "2_2") (pintype "passive"))
    )
    (net (code "213") (name "Net-(IC5-A0)") (class "Default")
      (node (ref "IC5") (pin "15") (pinfunction "A0_15") (pintype "input"))
      (node (ref "R112") (pin "2") (pinfunction "2_2") (pintype "passive"))
    )
    (net (code "214") (name "Net-(IC5-A1)") (class "Default")
      (node (ref "IC5") (pin "16") (pinfunction "A1_16") (pintype "input"))
      (node (ref "R113") (pin "2") (pinfunction "2_2") (pintype "passive"))
    )
    (net (code "215") (name "Net-(IC5-A2)") (class "Default")
      (node (ref "IC5") (pin "17") (pinfunction "A2_17") (pintype "input"))
      (node (ref "R114") (pin "2") (pinfunction "2_2") (pintype "passive"))
    )
    (net (code "216") (name "Net-(JP1-1)") (class "Default")
      (node (ref "HEADER-22P1") (pin "22") (pinfunction "22_22") (pintype "bidirectional"))
      (node (ref "JP1") (pin "P$1") (pinfunction "1_P$1") (pintype "passive"))
    )
    (net (code "217") (name "Net-(JP3-1)") (class "Default")
      (node (ref "HEADER-22P1") (pin "21") (pinfunction "21_21") (pintype "bidirectional"))
      (node (ref "JP3") (pin "P$1") (pinfunction "1_P$1") (pintype "passive"))
    )
    (net (code "218") (name "Net-(OPTO1-A)") (class "Default")
      (node (ref "LED1") (pin "-") (pinfunction "-_-") (pintype "passive"))
      (node (ref "OPTO1") (pin "1") (pinfunction "A_1") (pintype "passive"))
      (node (ref "Z1") (pin "C") (pinfunction "C_C") (pintype "passive"))
    )
    (net (code "219") (name "Net-(OPTO2-A)") (class "Default")
      (node (ref "LED2") (pin "-") (pinfunction "-_-") (pintype "passive"))
      (node (ref "OPTO2") (pin "1") (pinfunction "A_1") (pintype "passive"))
      (node (ref "Z2") (pin "C") (pinfunction "C_C") (pintype "passive"))
    )
    (net (code "220") (name "Net-(OPTO3-A)") (class "Default")
      (node (ref "LED3") (pin "-") (pinfunction "-_-") (pintype "passive"))
      (node (ref "OPTO3") (pin "1") (pinfunction "A_1") (pintype "passive"))
      (node (ref "Z3") (pin "C") (pinfunction "C_C") (pintype "passive"))
    )
    (net (code "221") (name "Net-(OPTO4-A)") (class "Default")
      (node (ref "LED4") (pin "-") (pinfunction "-_-") (pintype "passive"))
      (node (ref "OPTO4") (pin "1") (pinfunction "A_1") (pintype "passive"))
      (node (ref "Z4") (pin "C") (pinfunction "C_C") (pintype "passive"))
    )
    (net (code "222") (name "Net-(OPTO5-A)") (class "Default")
      (node (ref "LED5") (pin "-") (pinfunction "-_-") (pintype "passive"))
      (node (ref "OPTO5") (pin "1") (pinfunction "A_1") (pintype "passive"))
      (node (ref "Z5") (pin "C") (pinfunction "C_C") (pintype "passive"))
    )
    (net (code "223") (name "Net-(OPTO6-A)") (class "Default")
      (node (ref "LED6") (pin "-") (pinfunction "-_-") (pintype "passive"))
      (node (ref "OPTO6") (pin "1") (pinfunction "A_1") (pintype "passive"))
      (node (ref "Z6") (pin "C") (pinfunction "C_C") (pintype "passive"))
    )
    (net (code "224") (name "Net-(OPTO7-A)") (class "Default")
      (node (ref "LED7") (pin "-") (pinfunction "-_-") (pintype "passive"))
      (node (ref "OPTO7") (pin "1") (pinfunction "A_1") (pintype "passive"))
      (node (ref "Z7") (pin "C") (pinfunction "C_C") (pintype "passive"))
    )
    (net (code "225") (name "Net-(OPTO8-A)") (class "Default")
      (node (ref "LED8") (pin "-") (pinfunction "-_-") (pintype "passive"))
      (node (ref "OPTO8") (pin "1") (pinfunction "A_1") (pintype "passive"))
      (node (ref "Z8") (pin "C") (pinfunction "C_C") (pintype "passive"))
    )
    (net (code "226") (name "Net-(OPTO9-A)") (class "Default")
      (node (ref "LED9") (pin "-") (pinfunction "-_-") (pintype "passive"))
      (node (ref "OPTO9") (pin "1") (pinfunction "A_1") (pintype "passive"))
      (node (ref "Z9") (pin "C") (pinfunction "C_C") (pintype "passive"))
    )
    (net (code "227") (name "Net-(OPTO10-A)") (class "Default")
      (node (ref "LED10") (pin "-") (pinfunction "-_-") (pintype "passive"))
      (node (ref "OPTO10") (pin "1") (pinfunction "A_1") (pintype "passive"))
      (node (ref "Z10") (pin "C") (pinfunction "C_C") (pintype "passive"))
    )
    (net (code "228") (name "Net-(OPTO11-A)") (class "Default")
      (node (ref "LED11") (pin "-") (pinfunction "-_-") (pintype "passive"))
      (node (ref "OPTO11") (pin "1") (pinfunction "A_1") (pintype "passive"))
      (node (ref "Z11") (pin "C") (pinfunction "C_C") (pintype "passive"))
    )
    (net (code "229") (name "Net-(OPTO12-A)") (class "Default")
      (node (ref "LED12") (pin "-") (pinfunction "-_-") (pintype "passive"))
      (node (ref "OPTO12") (pin "1") (pinfunction "A_1") (pintype "passive"))
      (node (ref "Z12") (pin "C") (pinfunction "C_C") (pintype "passive"))
    )
    (net (code "230") (name "Net-(OPTO13-A)") (class "Default")
      (node (ref "LED13") (pin "-") (pinfunction "-_-") (pintype "passive"))
      (node (ref "OPTO13") (pin "1") (pinfunction "A_1") (pintype "passive"))
      (node (ref "Z13") (pin "C") (pinfunction "C_C") (pintype "passive"))
    )
    (net (code "231") (name "Net-(OPTO14-A)") (class "Default")
      (node (ref "LED14") (pin "-") (pinfunction "-_-") (pintype "passive"))
      (node (ref "OPTO14") (pin "1") (pinfunction "A_1") (pintype "passive"))
      (node (ref "Z14") (pin "C") (pinfunction "C_C") (pintype "passive"))
    )
    (net (code "232") (name "Net-(OPTO15-A)") (class "Default")
      (node (ref "LED15") (pin "-") (pinfunction "-_-") (pintype "passive"))
      (node (ref "OPTO15") (pin "1") (pinfunction "A_1") (pintype "passive"))
      (node (ref "Z15") (pin "C") (pinfunction "C_C") (pintype "passive"))
    )
    (net (code "233") (name "Net-(OPTO16-A)") (class "Default")
      (node (ref "LED16") (pin "-") (pinfunction "-_-") (pintype "passive"))
      (node (ref "OPTO16") (pin "1") (pinfunction "A_1") (pintype "passive"))
      (node (ref "Z16") (pin "C") (pinfunction "C_C") (pintype "passive"))
    )
    (net (code "234") (name "Net-(OPTO17-A)") (class "Default")
      (node (ref "LED17") (pin "-") (pinfunction "-_-") (pintype "passive"))
      (node (ref "OPTO17") (pin "1") (pinfunction "A_1") (pintype "passive"))
      (node (ref "Z17") (pin "C") (pinfunction "C_C") (pintype "passive"))
    )
    (net (code "235") (name "Net-(OPTO18-A)") (class "Default")
      (node (ref "LED18") (pin "-") (pinfunction "-_-") (pintype "passive"))
      (node (ref "OPTO18") (pin "1") (pinfunction "A_1") (pintype "passive"))
      (node (ref "Z18") (pin "C") (pinfunction "C_C") (pintype "passive"))
    )
    (net (code "236") (name "Net-(OPTO19-A)") (class "Default")
      (node (ref "LED19") (pin "-") (pinfunction "-_-") (pintype "passive"))
      (node (ref "OPTO19") (pin "1") (pinfunction "A_1") (pintype "passive"))
      (node (ref "Z19") (pin "C") (pinfunction "C_C") (pintype "passive"))
    )
    (net (code "237") (name "Net-(OPTO20-A)") (class "Default")
      (node (ref "LED20") (pin "-") (pinfunction "-_-") (pintype "passive"))
      (node (ref "OPTO20") (pin "1") (pinfunction "A_1") (pintype "passive"))
      (node (ref "Z20") (pin "C") (pinfunction "C_C") (pintype "passive"))
    )
    (net (code "238") (name "Net-(OPTO21-A)") (class "Default")
      (node (ref "LED21") (pin "-") (pinfunction "-_-") (pintype "passive"))
      (node (ref "OPTO21") (pin "1") (pinfunction "A_1") (pintype "passive"))
      (node (ref "Z21") (pin "C") (pinfunction "C_C") (pintype "passive"))
    )
    (net (code "239") (name "Net-(OPTO22-A)") (class "Default")
      (node (ref "LED22") (pin "-") (pinfunction "-_-") (pintype "passive"))
      (node (ref "OPTO22") (pin "1") (pinfunction "A_1") (pintype "passive"))
      (node (ref "Z22") (pin "C") (pinfunction "C_C") (pintype "passive"))
    )
    (net (code "240") (name "Net-(OPTO23-A)") (class "Default")
      (node (ref "LED23") (pin "-") (pinfunction "-_-") (pintype "passive"))
      (node (ref "OPTO23") (pin "1") (pinfunction "A_1") (pintype "passive"))
      (node (ref "Z23") (pin "C") (pinfunction "C_C") (pintype "passive"))
    )
    (net (code "241") (name "Net-(OPTO24-A)") (class "Default")
      (node (ref "LED24") (pin "-") (pinfunction "-_-") (pintype "passive"))
      (node (ref "OPTO24") (pin "1") (pinfunction "A_1") (pintype "passive"))
      (node (ref "Z24") (pin "C") (pinfunction "C_C") (pintype "passive"))
    )
    (net (code "242") (name "Net-(OPTO25-A)") (class "Default")
      (node (ref "LED25") (pin "-") (pinfunction "-_-") (pintype "passive"))
      (node (ref "OPTO25") (pin "1") (pinfunction "A_1") (pintype "passive"))
      (node (ref "Z25") (pin "C") (pinfunction "C_C") (pintype "passive"))
    )
    (net (code "243") (name "Net-(OPTO26-A)") (class "Default")
      (node (ref "LED26") (pin "-") (pinfunction "-_-") (pintype "passive"))
      (node (ref "OPTO26") (pin "1") (pinfunction "A_1") (pintype "passive"))
      (node (ref "Z26") (pin "C") (pinfunction "C_C") (pintype "passive"))
    )
    (net (code "244") (name "Net-(OPTO27-A)") (class "Default")
      (node (ref "LED27") (pin "-") (pinfunction "-_-") (pintype "passive"))
      (node (ref "OPTO27") (pin "1") (pinfunction "A_1") (pintype "passive"))
      (node (ref "Z27") (pin "C") (pinfunction "C_C") (pintype "passive"))
    )
    (net (code "245") (name "Net-(OPTO28-A)") (class "Default")
      (node (ref "LED28") (pin "-") (pinfunction "-_-") (pintype "passive"))
      (node (ref "OPTO28") (pin "1") (pinfunction "A_1") (pintype "passive"))
      (node (ref "Z28") (pin "C") (pinfunction "C_C") (pintype "passive"))
    )
    (net (code "246") (name "Net-(OPTO29-A)") (class "Default")
      (node (ref "LED29") (pin "-") (pinfunction "-_-") (pintype "passive"))
      (node (ref "OPTO29") (pin "1") (pinfunction "A_1") (pintype "passive"))
      (node (ref "Z29") (pin "C") (pinfunction "C_C") (pintype "passive"))
    )
    (net (code "247") (name "Net-(OPTO30-A)") (class "Default")
      (node (ref "LED30") (pin "-") (pinfunction "-_-") (pintype "passive"))
      (node (ref "OPTO30") (pin "1") (pinfunction "A_1") (pintype "passive"))
      (node (ref "Z30") (pin "C") (pinfunction "C_C") (pintype "passive"))
    )
    (net (code "248") (name "Net-(OPTO31-A)") (class "Default")
      (node (ref "LED31") (pin "-") (pinfunction "-_-") (pintype "passive"))
      (node (ref "OPTO31") (pin "1") (pinfunction "A_1") (pintype "passive"))
      (node (ref "Z31") (pin "C") (pinfunction "C_C") (pintype "passive"))
    )
    (net (code "249") (name "Net-(OPTO32-A)") (class "Default")
      (node (ref "LED32") (pin "-") (pinfunction "-_-") (pintype "passive"))
      (node (ref "OPTO32") (pin "1") (pinfunction "A_1") (pintype "passive"))
      (node (ref "Z32") (pin "C") (pinfunction "C_C") (pintype "passive"))
    )
    (net (code "250") (name "Net-(OPTO33-A)") (class "Default")
      (node (ref "LED33") (pin "-") (pinfunction "-_-") (pintype "passive"))
      (node (ref "OPTO33") (pin "1") (pinfunction "A_1") (pintype "passive"))
      (node (ref "Z33") (pin "C") (pinfunction "C_C") (pintype "passive"))
    )
    (net (code "251") (name "Net-(OPTO34-A)") (class "Default")
      (node (ref "LED34") (pin "-") (pinfunction "-_-") (pintype "passive"))
      (node (ref "OPTO34") (pin "1") (pinfunction "A_1") (pintype "passive"))
      (node (ref "Z34") (pin "C") (pinfunction "C_C") (pintype "passive"))
    )
    (net (code "252") (name "Net-(OPTO35-A)") (class "Default")
      (node (ref "LED35") (pin "-") (pinfunction "-_-") (pintype "passive"))
      (node (ref "OPTO35") (pin "1") (pinfunction "A_1") (pintype "passive"))
      (node (ref "Z35") (pin "C") (pinfunction "C_C") (pintype "passive"))
    )
    (net (code "253") (name "Net-(OPTO36-A)") (class "Default")
      (node (ref "LED36") (pin "-") (pinfunction "-_-") (pintype "passive"))
      (node (ref "OPTO36") (pin "1") (pinfunction "A_1") (pintype "passive"))
      (node (ref "Z36") (pin "C") (pinfunction "C_C") (pintype "passive"))
    )
    (net (code "254") (name "Net-(OPTO37-A)") (class "Default")
      (node (ref "LED37") (pin "-") (pinfunction "-_-") (pintype "passive"))
      (node (ref "OPTO37") (pin "1") (pinfunction "A_1") (pintype "passive"))
      (node (ref "Z37") (pin "C") (pinfunction "C_C") (pintype "passive"))
    )
    (net (code "255") (name "Net-(OPTO38-A)") (class "Default")
      (node (ref "LED38") (pin "-") (pinfunction "-_-") (pintype "passive"))
      (node (ref "OPTO38") (pin "1") (pinfunction "A_1") (pintype "passive"))
      (node (ref "Z38") (pin "C") (pinfunction "C_C") (pintype "passive"))
    )
    (net (code "256") (name "Net-(OPTO39-A)") (class "Default")
      (node (ref "LED39") (pin "-") (pinfunction "-_-") (pintype "passive"))
      (node (ref "OPTO39") (pin "1") (pinfunction "A_1") (pintype "passive"))
      (node (ref "Z39") (pin "C") (pinfunction "C_C") (pintype "passive"))
    )
    (net (code "257") (name "Net-(OPTO40-A)") (class "Default")
      (node (ref "LED40") (pin "-") (pinfunction "-_-") (pintype "passive"))
      (node (ref "OPTO40") (pin "1") (pinfunction "A_1") (pintype "passive"))
      (node (ref "Z40") (pin "C") (pinfunction "C_C") (pintype "passive"))
    )
    (net (code "258") (name "Net-(OPTO41-A)") (class "Default")
      (node (ref "LED41") (pin "-") (pinfunction "-_-") (pintype "passive"))
      (node (ref "OPTO41") (pin "1") (pinfunction "A_1") (pintype "passive"))
      (node (ref "Z41") (pin "C") (pinfunction "C_C") (pintype "passive"))
    )
    (net (code "259") (name "Net-(OPTO42-A)") (class "Default")
      (node (ref "LED42") (pin "-") (pinfunction "-_-") (pintype "passive"))
      (node (ref "OPTO42") (pin "1") (pinfunction "A_1") (pintype "passive"))
      (node (ref "Z42") (pin "C") (pinfunction "C_C") (pintype "passive"))
    )
    (net (code "260") (name "Net-(OPTO43-A)") (class "Default")
      (node (ref "LED43") (pin "-") (pinfunction "-_-") (pintype "passive"))
      (node (ref "OPTO43") (pin "1") (pinfunction "A_1") (pintype "passive"))
      (node (ref "Z43") (pin "C") (pinfunction "C_C") (pintype "passive"))
    )
    (net (code "261") (name "Net-(OPTO44-A)") (class "Default")
      (node (ref "LED44") (pin "-") (pinfunction "-_-") (pintype "passive"))
      (node (ref "OPTO44") (pin "1") (pinfunction "A_1") (pintype "passive"))
      (node (ref "Z44") (pin "C") (pinfunction "C_C") (pintype "passive"))
    )
    (net (code "262") (name "Net-(OPTO45-A)") (class "Default")
      (node (ref "LED45") (pin "-") (pinfunction "-_-") (pintype "passive"))
      (node (ref "OPTO45") (pin "1") (pinfunction "A_1") (pintype "passive"))
      (node (ref "Z45") (pin "C") (pinfunction "C_C") (pintype "passive"))
    )
    (net (code "263") (name "Net-(OPTO46-A)") (class "Default")
      (node (ref "LED46") (pin "-") (pinfunction "-_-") (pintype "passive"))
      (node (ref "OPTO46") (pin "1") (pinfunction "A_1") (pintype "passive"))
      (node (ref "Z46") (pin "C") (pinfunction "C_C") (pintype "passive"))
    )
    (net (code "264") (name "Net-(OPTO47-A)") (class "Default")
      (node (ref "LED47") (pin "-") (pinfunction "-_-") (pintype "passive"))
      (node (ref "OPTO47") (pin "1") (pinfunction "A_1") (pintype "passive"))
      (node (ref "Z47") (pin "C") (pinfunction "C_C") (pintype "passive"))
    )
    (net (code "265") (name "Net-(OPTO48-A)") (class "Default")
      (node (ref "LED48") (pin "-") (pinfunction "-_-") (pintype "passive"))
      (node (ref "OPTO48") (pin "1") (pinfunction "A_1") (pintype "passive"))
      (node (ref "Z48") (pin "C") (pinfunction "C_C") (pintype "passive"))
    )
    (net (code "266") (name "Net-(Q1-B)") (class "Default")
      (node (ref "Q1") (pin "1") (pinfunction "B_1") (pintype "passive"))
      (node (ref "U49") (pin "3") (pinfunction "ET_3") (pintype "passive"))
    )
    (net (code "267") (name "Net-(Q1-C)") (class "Default")
      (node (ref "D1") (pin "A") (pinfunction "A_A") (pintype "passive"))
      (node (ref "K1") (pin "A2") (pinfunction "A2_A2") (pintype "passive"))
      (node (ref "Q1") (pin "3") (pinfunction "C_3") (pintype "passive"))
    )
    (net (code "268") (name "Net-(U49-A)") (class "Default")
      (node (ref "D146") (pin "-") (pinfunction "-_-") (pintype "passive"))
      (node (ref "U49") (pin "1") (pinfunction "A_1") (pintype "passive"))
    )
    (net (code "269") (name "Net-(U49-CT)") (class "Default")
      (node (ref "R116") (pin "1") (pinfunction "1_1") (pintype "passive"))
      (node (ref "U49") (pin "4") (pinfunction "CT_4") (pintype "passive"))
    )
    (net (code "270") (name "RELAY") (class "Default")
      (node (ref "R115") (pin "2") (pinfunction "2_2") (pintype "passive"))
      (node (ref "SV1") (pin "1") (pinfunction "1_1") (pintype "passive"))
    )
    (net (code "271") (name "VCC") (class "Default")
      (node (ref "D1") (pin "C") (pinfunction "K_C") (pintype "passive"))
      (node (ref "IC1") (pin "9") (pinfunction "VDD_9") (pintype "power_in"))
      (node (ref "IC4") (pin "9") (pinfunction "VDD_9") (pintype "power_in"))
      (node (ref "IC5") (pin "9") (pinfunction "VDD_9") (pintype "power_in"))
      (node (ref "JP2") (pin "1") (pinfunction "1_1") (pintype "passive"))
      (node (ref "JP2") (pin "3") (pinfunction "3_3") (pintype "passive"))
      (node (ref "JP2") (pin "5") (pinfunction "5_5") (pintype "passive"))
      (node (ref "JP2") (pin "7") (pinfunction "7_7") (pintype "passive"))
      (node (ref "K1") (pin "A1") (pinfunction "A1_A1") (pintype "passive"))
      (node (ref "R100") (pin "2") (pinfunction "2_2") (pintype "passive"))
      (node (ref "R101") (pin "2") (pinfunction "2_2") (pintype "passive"))
      (node (ref "R102") (pin "2") (pinfunction "2_2") (pintype "passive"))
      (node (ref "R103") (pin "1") (pinfunction "1_1") (pintype "passive"))
      (node (ref "R107") (pin "2") (pinfunction "2_2") (pintype "passive"))
      (node (ref "R108") (pin "1") (pinfunction "1_1") (pintype "passive"))
      (node (ref "R111") (pin "1") (pinfunction "1_1") (pintype "passive"))
      (node (ref "R113") (pin "1") (pinfunction "1_1") (pintype "passive"))
      (node (ref "R116") (pin "2") (pinfunction "2_2") (pintype "passive"))
      (node (ref "R49") (pin "2") (pinfunction "2_2") (pintype "passive"))
      (node (ref "R50") (pin "2") (pinfunction "2_2") (pintype "passive"))
      (node (ref "R51") (pin "2") (pinfunction "2_2") (pintype "passive"))
      (node (ref "R52") (pin "2") (pinfunction "2_2") (pintype "passive"))
      (node (ref "R53") (pin "2") (pinfunction "2_2") (pintype "passive"))
      (node (ref "R54") (pin "2") (pinfunction "2_2") (pintype "passive"))
      (node (ref "R55") (pin "2") (pinfunction "2_2") (pintype "passive"))
      (node (ref "R56") (pin "2") (pinfunction "2_2") (pintype "passive"))
      (node (ref "R57") (pin "2") (pinfunction "2_2") (pintype "passive"))
      (node (ref "R58") (pin "2") (pinfunction "2_2") (pintype "passive"))
      (node (ref "R59") (pin "2") (pinfunction "2_2") (pintype "passive"))
      (node (ref "R60") (pin "2") (pinfunction "2_2") (pintype "passive"))
      (node (ref "R61") (pin "2") (pinfunction "2_2") (pintype "passive"))
      (node (ref "R62") (pin "2") (pinfunction "2_2") (pintype "passive"))
      (node (ref "R63") (pin "2") (pinfunction "2_2") (pintype "passive"))
      (node (ref "R64") (pin "2") (pinfunction "2_2") (pintype "passive"))
      (node (ref "R65") (pin "2") (pinfunction "2_2") (pintype "passive"))
      (node (ref "R66") (pin "2") (pinfunction "2_2") (pintype "passive"))
      (node (ref "R67") (pin "2") (pinfunction "2_2") (pintype "passive"))
      (node (ref "R68") (pin "2") (pinfunction "2_2") (pintype "passive"))
      (node (ref "R69") (pin "2") (pinfunction "2_2") (pintype "passive"))
      (node (ref "R70") (pin "2") (pinfunction "2_2") (pintype "passive"))
      (node (ref "R71") (pin "2") (pinfunction "2_2") (pintype "passive"))
      (node (ref "R72") (pin "2") (pinfunction "2_2") (pintype "passive"))
      (node (ref "R73") (pin "2") (pinfunction "2_2") (pintype "passive"))
      (node (ref "R74") (pin "2") (pinfunction "2_2") (pintype "passive"))
      (node (ref "R75") (pin "2") (pinfunction "2_2") (pintype "passive"))
      (node (ref "R76") (pin "2") (pinfunction "2_2") (pintype "passive"))
      (node (ref "R77") (pin "2") (pinfunction "2_2") (pintype "passive"))
      (node (ref "R78") (pin "2") (pinfunction "2_2") (pintype "passive"))
      (node (ref "R79") (pin "2") (pinfunction "2_2") (pintype "passive"))
      (node (ref "R80") (pin "2") (pinfunction "2_2") (pintype "passive"))
      (node (ref "R81") (pin "2") (pinfunction "2_2") (pintype "passive"))
      (node (ref "R82") (pin "2") (pinfunction "2_2") (pintype "passive"))
      (node (ref "R83") (pin "2") (pinfunction "2_2") (pintype "passive"))
      (node (ref "R84") (pin "2") (pinfunction "2_2") (pintype "passive"))
      (node (ref "R85") (pin "2") (pinfunction "2_2") (pintype "passive"))
      (node (ref "R86") (pin "2") (pinfunction "2_2") (pintype "passive"))
      (node (ref "R87") (pin "2") (pinfunction "2_2") (pintype "passive"))
      (node (ref "R88") (pin "2") (pinfunction "2_2") (pintype "passive"))
      (node (ref "R89") (pin "2") (pinfunction "2_2") (pintype "passive"))
      (node (ref "R90") (pin "2") (pinfunction "2_2") (pintype "passive"))
      (node (ref "R91") (pin "2") (pinfunction "2_2") (pintype "passive"))
      (node (ref "R92") (pin "2") (pinfunction "2_2") (pintype "passive"))
      (node (ref "R93") (pin "2") (pinfunction "2_2") (pintype "passive"))
      (node (ref "R94") (pin "2") (pinfunction "2_2") (pintype "passive"))
      (node (ref "R95") (pin "2") (pinfunction "2_2") (pintype "passive"))
      (node (ref "R96") (pin "2") (pinfunction "2_2") (pintype "passive"))
      (node (ref "R97") (pin "2") (pinfunction "2_2") (pintype "passive"))
      (node (ref "R98") (pin "2") (pinfunction "2_2") (pintype "passive"))
      (node (ref "R99") (pin "2") (pinfunction "2_2") (pintype "passive"))
      (node (ref "SV1") (pin "9") (pinfunction "9_9") (pintype "passive"))
      (node (ref "TTL-RS1") (pin "VCC") (pinfunction "VCC_VCC") (pintype "bidirectional"))
    )
    (net (code "272") (name "unconnected-(IC1-INTA-Pad20)") (class "Default")
      (node (ref "IC1") (pin "20") (pinfunction "INTA_20") (pintype "output"))
    )
    (net (code "273") (name "unconnected-(IC1-INTB-Pad19)") (class "Default")
      (node (ref "IC1") (pin "19") (pinfunction "INTB_19") (pintype "output"))
    )
    (net (code "274") (name "unconnected-(IC4-INTA-Pad20)") (class "Default")
      (node (ref "IC4") (pin "20") (pinfunction "INTA_20") (pintype "output"))
    )
    (net (code "275") (name "unconnected-(IC4-INTB-Pad19)") (class "Default")
      (node (ref "IC4") (pin "19") (pinfunction "INTB_19") (pintype "output"))
    )
    (net (code "276") (name "unconnected-(IC5-INTA-Pad20)") (class "Default")
      (node (ref "IC5") (pin "20") (pinfunction "INTA_20") (pintype "output"))
    )
    (net (code "277") (name "unconnected-(IC5-INTB-Pad19)") (class "Default")
      (node (ref "IC5") (pin "19") (pinfunction "INTB_19") (pintype "output"))
    )
  )
)
